# harp_timestamp_generator.net
KiCad netlist of a schematic drawn in EAGLE
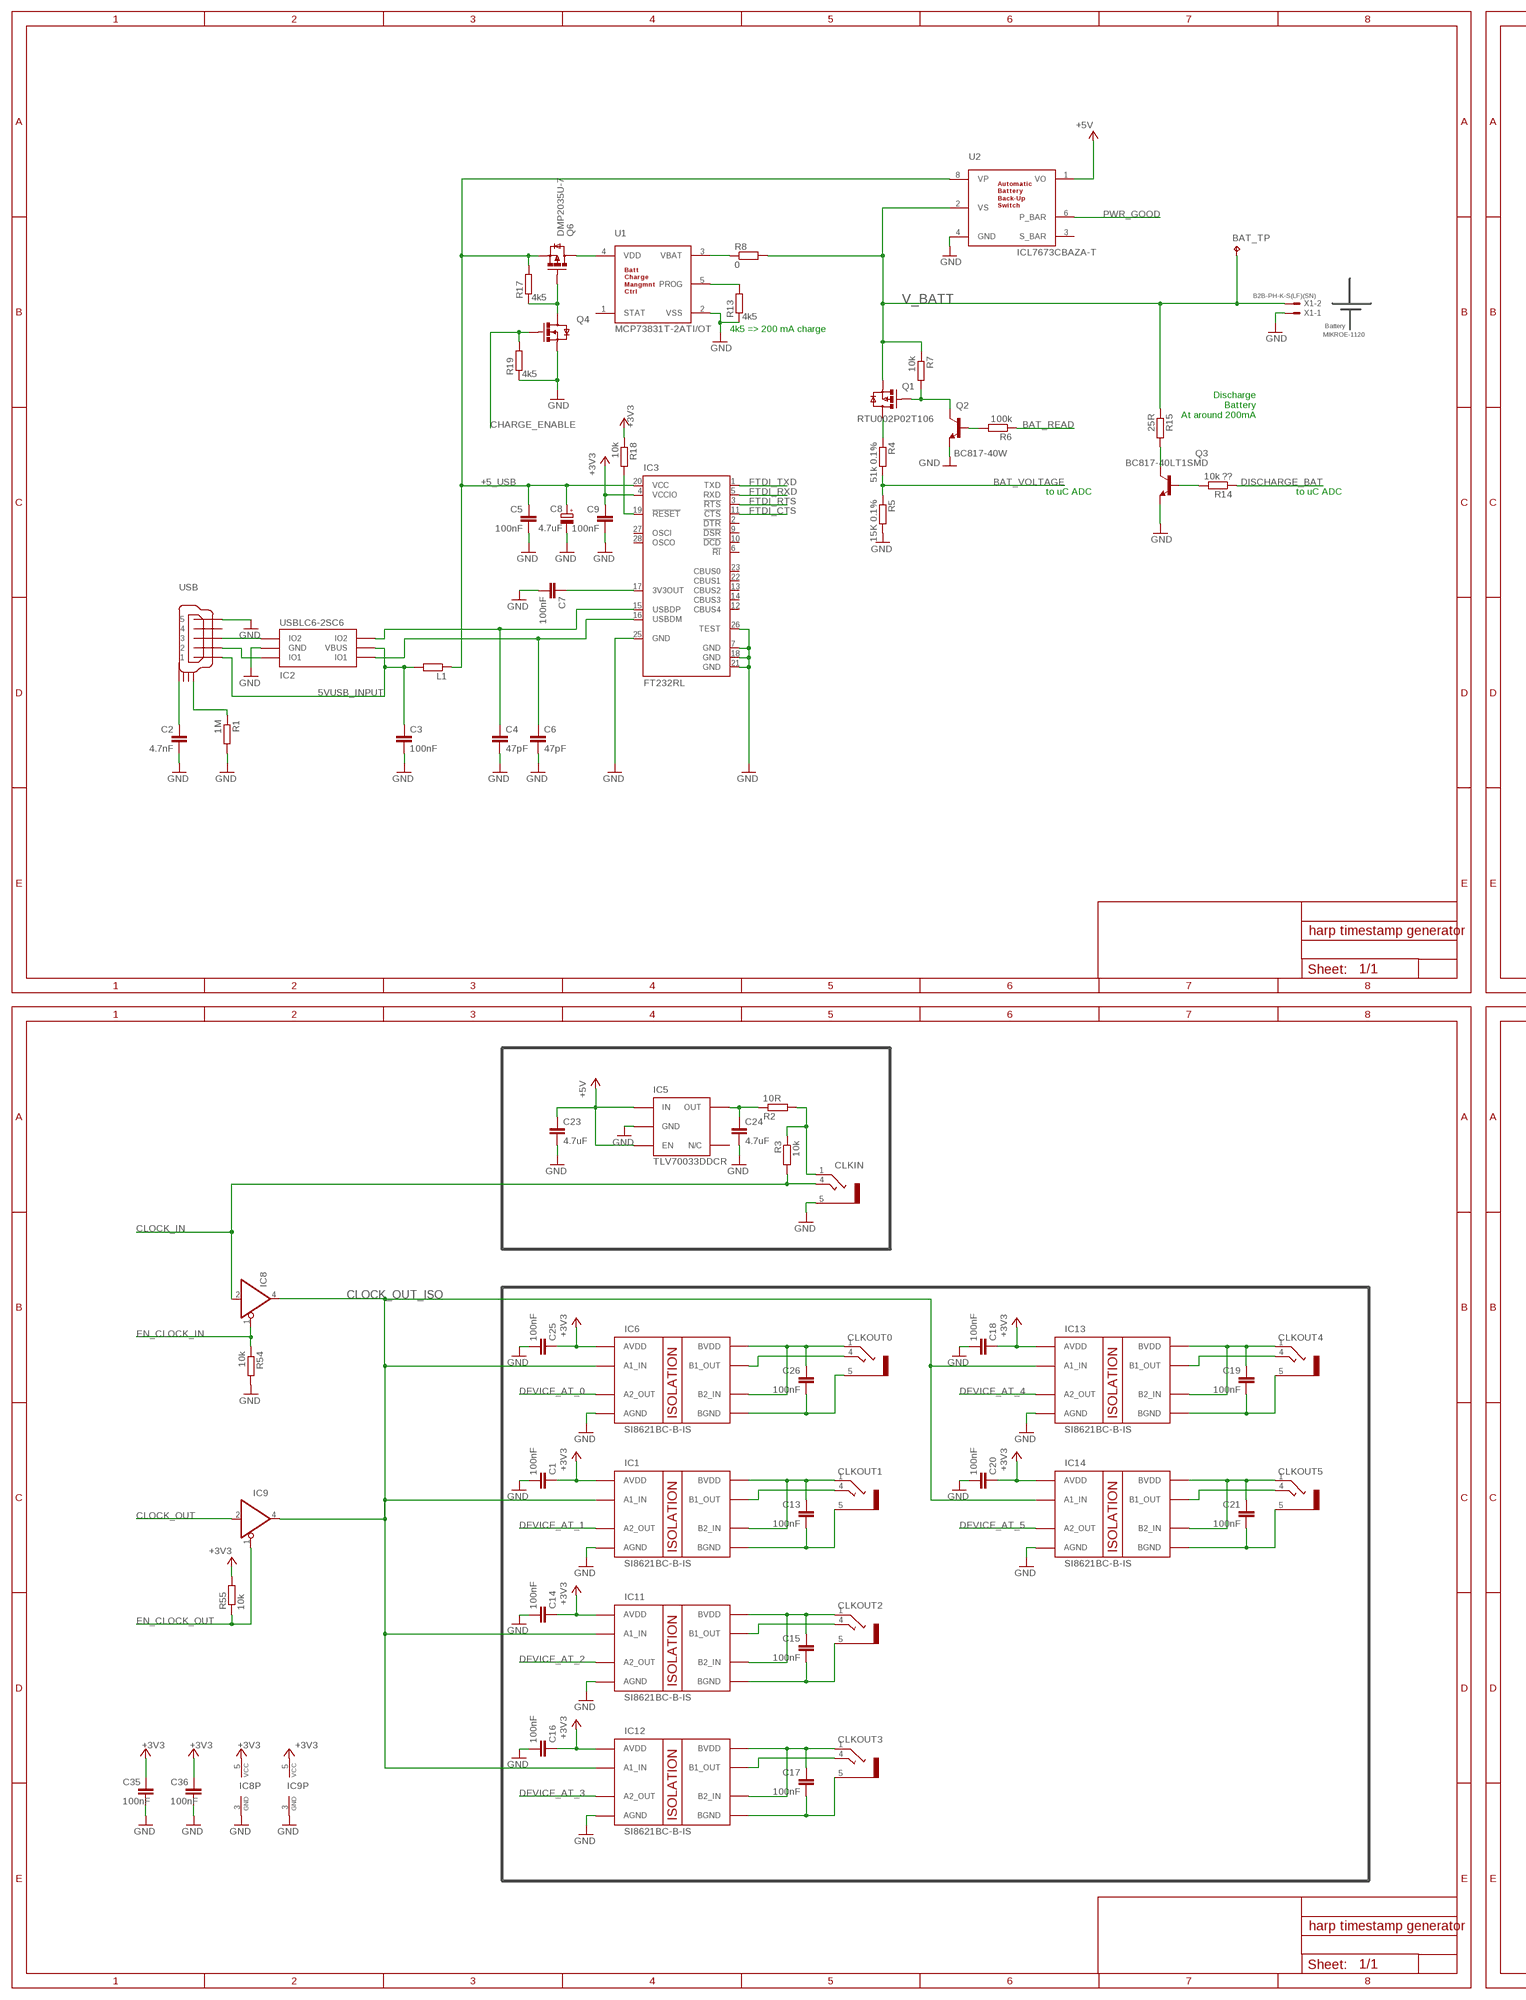
[diagram p0: schematic, sheet 1, part 1 of 3]
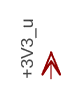
[diagram p1: schematic, sheet 1, part 2 of 3]
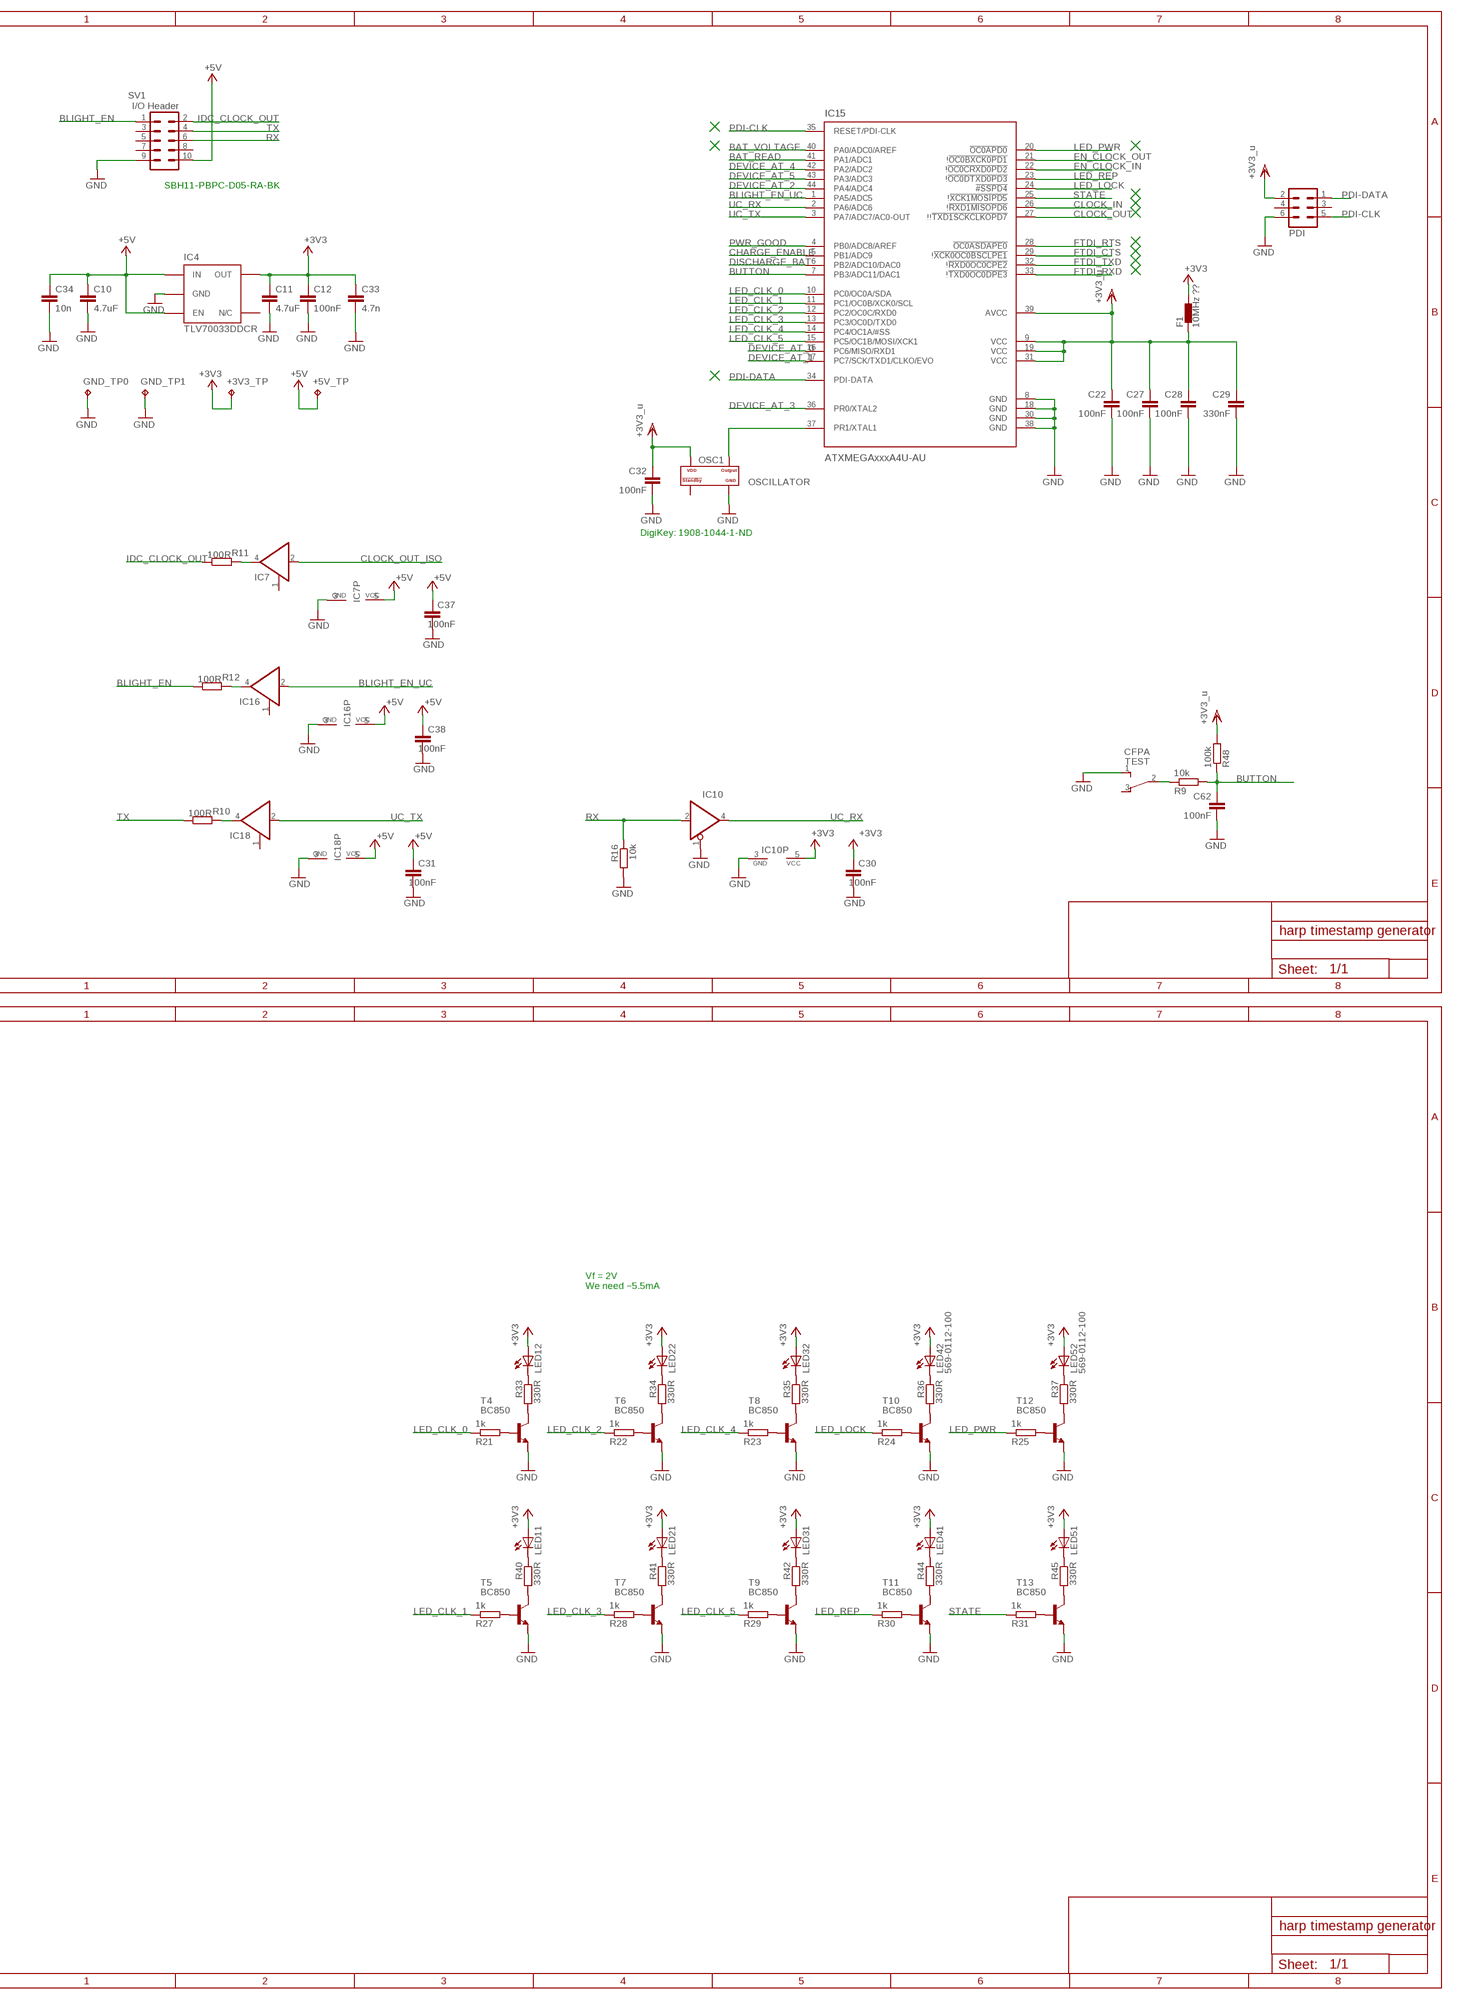
[diagram p2: schematic, sheet 1, part 3 of 3]

(export (version "E")
  (design (tool "Eeschema 10.0.6"))
  (components
    (comp (ref "+3V3_TP")
      (value "TPPAD1-13")
      (footprint "eagle-import:P1-13")
      (fields (field (name "MPN") "n.a."))
      (libsource (lib "eagle-import") (part "TPPAD1-13"))
    )
    (comp (ref "+5V_TP")
      (value "TPPAD1-13")
      (footprint "eagle-import:P1-13")
      (fields (field (name "MPN") "n.a."))
      (libsource (lib "eagle-import") (part "TPPAD1-13"))
    )
    (comp (ref "BAT_TP")
      (value "TPPAD1-13")
      (footprint "eagle-import:P1-13")
      (fields (field (name "MPN") "n.a."))
      (libsource (lib "eagle-import") (part "TPPAD1-13"))
    )
    (comp (ref "C1")
      (value "100nF")
      (footprint "eagle-import:C0402")
      (fields (field (name "MPN") "MC0402B104K160CT"))
      (libsource (lib "eagle-import") (part "C-EUC0402"))
    )
    (comp (ref "C2")
      (value "4.7nF")
      (footprint "eagle-import:C0402")
      (fields (field (name "MPN") "885012205084"))
      (libsource (lib "eagle-import") (part "C-EUC0402"))
    )
    (comp (ref "C3")
      (value "100nF")
      (footprint "eagle-import:C0402")
      (fields (field (name "MPN") "MC0402B104K160CT"))
      (libsource (lib "eagle-import") (part "C-EUC0402"))
    )
    (comp (ref "C4")
      (value "47pF")
      (footprint "eagle-import:C0402")
      (fields (field (name "MPN") "04025A470JAT2A"))
      (libsource (lib "eagle-import") (part "C-EUC0402"))
    )
    (comp (ref "C5")
      (value "100nF")
      (footprint "eagle-import:C0402")
      (fields (field (name "MPN") "MC0402B104K160CT"))
      (libsource (lib "eagle-import") (part "C-EUC0402"))
    )
    (comp (ref "C6")
      (value "47pF")
      (footprint "eagle-import:C0402")
      (fields (field (name "MPN") "04025A470JAT2A"))
      (libsource (lib "eagle-import") (part "C-EUC0402"))
    )
    (comp (ref "C7")
      (value "100nF")
      (footprint "eagle-import:C0402")
      (fields (field (name "MPN") "MC0402B104K160CT"))
      (libsource (lib "eagle-import") (part "C-EUC0402"))
    )
    (comp (ref "C8")
      (value "4.7uF")
      (footprint "eagle-import:A_3216-18W")
      (fields (field (name "MPN") "TAJA475K016UNJ"))
      (libsource (lib "eagle-import") (part "CPOL-EUA/3216-18W"))
    )
    (comp (ref "C9")
      (value "100nF")
      (footprint "eagle-import:C0402")
      (fields (field (name "MPN") "MC0402B104K160CT"))
      (libsource (lib "eagle-import") (part "C-EUC0402"))
    )
    (comp (ref "C10")
      (value "4.7uF")
      (footprint "eagle-import:C0603")
      (fields (field (name "MPN") "C1608X6S1C475K080AC"))
      (libsource (lib "eagle-import") (part "C-EUC0603"))
    )
    (comp (ref "C11")
      (value "4.7uF")
      (footprint "eagle-import:C0603")
      (fields (field (name "MPN") "C1608X6S1C475K080AC"))
      (libsource (lib "eagle-import") (part "C-EUC0603"))
    )
    (comp (ref "C12")
      (value "100nF")
      (footprint "eagle-import:C0402")
      (fields (field (name "MPN") "MC0402B104K160CT"))
      (libsource (lib "eagle-import") (part "C-EUC0402"))
    )
    (comp (ref "C13")
      (value "100nF")
      (footprint "eagle-import:C0402")
      (fields (field (name "MPN") "MC0402B104K160CT"))
      (libsource (lib "eagle-import") (part "C-EUC0402"))
    )
    (comp (ref "C14")
      (value "100nF")
      (footprint "eagle-import:C0402")
      (fields (field (name "MPN") "MC0402B104K160CT"))
      (libsource (lib "eagle-import") (part "C-EUC0402"))
    )
    (comp (ref "C15")
      (value "100nF")
      (footprint "eagle-import:C0402")
      (fields (field (name "MPN") "MC0402B104K160CT"))
      (libsource (lib "eagle-import") (part "C-EUC0402"))
    )
    (comp (ref "C16")
      (value "100nF")
      (footprint "eagle-import:C0402")
      (fields (field (name "MPN") "MC0402B104K160CT"))
      (libsource (lib "eagle-import") (part "C-EUC0402"))
    )
    (comp (ref "C17")
      (value "100nF")
      (footprint "eagle-import:C0402")
      (fields (field (name "MPN") "MC0402B104K160CT"))
      (libsource (lib "eagle-import") (part "C-EUC0402"))
    )
    (comp (ref "C18")
      (value "100nF")
      (footprint "eagle-import:C0402")
      (fields (field (name "MPN") "MC0402B104K160CT"))
      (libsource (lib "eagle-import") (part "C-EUC0402"))
    )
    (comp (ref "C19")
      (value "100nF")
      (footprint "eagle-import:C0402")
      (fields (field (name "MPN") "MC0402B104K160CT"))
      (libsource (lib "eagle-import") (part "C-EUC0402"))
    )
    (comp (ref "C20")
      (value "100nF")
      (footprint "eagle-import:C0402")
      (fields (field (name "MPN") "MC0402B104K160CT"))
      (libsource (lib "eagle-import") (part "C-EUC0402"))
    )
    (comp (ref "C21")
      (value "100nF")
      (footprint "eagle-import:C0402")
      (fields (field (name "MPN") "MC0402B104K160CT"))
      (libsource (lib "eagle-import") (part "C-EUC0402"))
    )
    (comp (ref "C22")
      (value "100nF")
      (footprint "eagle-import:C0402")
      (libsource (lib "eagle-import") (part "C-EUC0402"))
    )
    (comp (ref "C23")
      (value "4.7uF")
      (footprint "eagle-import:C0603")
      (fields (field (name "MPN") "C1608X6S1C475K080AC"))
      (libsource (lib "eagle-import") (part "C-EUC0603"))
    )
    (comp (ref "C24")
      (value "4.7uF")
      (footprint "eagle-import:C0603")
      (fields (field (name "MPN") "C1608X6S1C475K080AC"))
      (libsource (lib "eagle-import") (part "C-EUC0603"))
    )
    (comp (ref "C25")
      (value "100nF")
      (footprint "eagle-import:C0402")
      (fields (field (name "MPN") "MC0402B104K160CT"))
      (libsource (lib "eagle-import") (part "C-EUC0402"))
    )
    (comp (ref "C26")
      (value "100nF")
      (footprint "eagle-import:C0402")
      (fields (field (name "MPN") "MC0402B104K160CT"))
      (libsource (lib "eagle-import") (part "C-EUC0402"))
    )
    (comp (ref "C27")
      (value "100nF")
      (footprint "eagle-import:C0402")
      (libsource (lib "eagle-import") (part "C-EUC0402"))
    )
    (comp (ref "C28")
      (value "100nF")
      (footprint "eagle-import:C0402")
      (libsource (lib "eagle-import") (part "C-EUC0402"))
    )
    (comp (ref "C29")
      (value "330nF")
      (footprint "eagle-import:C0402")
      (libsource (lib "eagle-import") (part "C-EUC0402"))
    )
    (comp (ref "C30")
      (value "100nF")
      (footprint "eagle-import:C0402")
      (fields (field (name "MPN") "MC0402B104K160CT"))
      (libsource (lib "eagle-import") (part "C-EUC0402"))
    )
    (comp (ref "C31")
      (value "100nF")
      (footprint "eagle-import:C0402")
      (fields (field (name "MPN") "MC0402B104K160CT"))
      (libsource (lib "eagle-import") (part "C-EUC0402"))
    )
    (comp (ref "C32")
      (value "100nF")
      (footprint "eagle-import:C0402")
      (libsource (lib "eagle-import") (part "C-EUC0402"))
    )
    (comp (ref "C33")
      (value "4.7n")
      (footprint "eagle-import:C0402")
      (fields (field (name "MPN") "??"))
      (libsource (lib "eagle-import") (part "C-EUC0402"))
    )
    (comp (ref "C34")
      (value "10n")
      (footprint "eagle-import:C0402")
      (fields (field (name "MPN") "??"))
      (libsource (lib "eagle-import") (part "C-EUC0402"))
    )
    (comp (ref "C35")
      (value "100nF")
      (footprint "eagle-import:C0402")
      (fields (field (name "MPN") "MC0402B104K160CT"))
      (libsource (lib "eagle-import") (part "C-EUC0402"))
    )
    (comp (ref "C36")
      (value "100nF")
      (footprint "eagle-import:C0402")
      (fields (field (name "MPN") "MC0402B104K160CT"))
      (libsource (lib "eagle-import") (part "C-EUC0402"))
    )
    (comp (ref "C37")
      (value "100nF")
      (footprint "eagle-import:C0402")
      (fields (field (name "MPN") "MC0402B104K160CT"))
      (libsource (lib "eagle-import") (part "C-EUC0402"))
    )
    (comp (ref "C38")
      (value "100nF")
      (footprint "eagle-import:C0402")
      (fields (field (name "MPN") "MC0402B104K160CT"))
      (libsource (lib "eagle-import") (part "C-EUC0402"))
    )
    (comp (ref "C62")
      (value "100nF")
      (footprint "eagle-import:C0402")
      (libsource (lib "eagle-import") (part "C-EUC0402"))
    )
    (comp (ref "CLKIN")
      (value "CLCK_JACK")
      (footprint "eagle-import:35RASMT2BHNTRX")
      (fields (field (name "MPN") "35RASMT2BHNTRX"))
      (libsource (lib "eagle-import") (part "STEREO_JACK"))
    )
    (comp (ref "CLKOUT0")
      (value "CLCK_JACK")
      (footprint "eagle-import:35RASMT2BHNTRX")
      (fields (field (name "MPN") "35RASMT2BHNTRX"))
      (libsource (lib "eagle-import") (part "STEREO_JACK"))
    )
    (comp (ref "CLKOUT1")
      (value "CLCK_JACK")
      (footprint "eagle-import:35RASMT2BHNTRX")
      (fields (field (name "MPN") "35RASMT2BHNTRX"))
      (libsource (lib "eagle-import") (part "STEREO_JACK"))
    )
    (comp (ref "CLKOUT2")
      (value "CLCK_JACK")
      (footprint "eagle-import:35RASMT2BHNTRX")
      (fields (field (name "MPN") "35RASMT2BHNTRX"))
      (libsource (lib "eagle-import") (part "STEREO_JACK"))
    )
    (comp (ref "CLKOUT3")
      (value "CLCK_JACK")
      (footprint "eagle-import:35RASMT2BHNTRX")
      (fields (field (name "MPN") "35RASMT2BHNTRX"))
      (libsource (lib "eagle-import") (part "STEREO_JACK"))
    )
    (comp (ref "CLKOUT4")
      (value "CLCK_JACK")
      (footprint "eagle-import:35RASMT2BHNTRX")
      (fields (field (name "MPN") "35RASMT2BHNTRX"))
      (libsource (lib "eagle-import") (part "STEREO_JACK"))
    )
    (comp (ref "CLKOUT5")
      (value "CLCK_JACK")
      (footprint "eagle-import:35RASMT2BHNTRX")
      (fields (field (name "MPN") "35RASMT2BHNTRX"))
      (libsource (lib "eagle-import") (part "STEREO_JACK"))
    )
    (comp (ref "F1")
      (value "10MHz ??")
      (footprint "eagle-import:R0603")
      (libsource (lib "eagle-import") (part "BLM15HF0603"))
    )
    (comp (ref "GND_TP0")
      (value "TPPAD1-13")
      (footprint "eagle-import:P1-13")
      (fields (field (name "MPN") "n.a."))
      (libsource (lib "eagle-import") (part "TPPAD1-13"))
    )
    (comp (ref "GND_TP1")
      (value "TPPAD1-13")
      (footprint "eagle-import:P1-13")
      (fields (field (name "MPN") "n.a."))
      (libsource (lib "eagle-import") (part "TPPAD1-13"))
    )
    (comp (ref "IC1")
      (value "SI8621BC-B-IS")
      (footprint "eagle-import:SOIC8")
      (fields (field (name "MPN") "Si8621BC-B-IS"))
      (libsource (lib "eagle-import") (part "SI8621BC-B-IS"))
    )
    (comp (ref "IC2")
      (value "USBLC6-2SC6")
      (footprint "eagle-import:SOT23-6L")
      (libsource (lib "eagle-import") (part "USBLC6-2"))
    )
    (comp (ref "IC3")
      (value "FT232RL")
      (footprint "eagle-import:SSOP28")
      (fields (field (name "MPN") "FT232RL-REEL"))
      (libsource (lib "eagle-import") (part "FT232RL"))
    )
    (comp (ref "IC4")
      (value "TLV70033DDCR")
      (footprint "eagle-import:TSOT23-5")
      (libsource (lib "eagle-import") (part "TLV700XX"))
    )
    (comp (ref "IC5")
      (value "TLV70033DDCR")
      (footprint "eagle-import:TSOT23-5")
      (libsource (lib "eagle-import") (part "TLV700XX"))
    )
    (comp (ref "IC6")
      (value "SI8621BC-B-IS")
      (footprint "eagle-import:SOIC8")
      (fields (field (name "MPN") "Si8621BC-B-IS"))
      (libsource (lib "eagle-import") (part "SI8621BC-B-IS"))
    )
    (comp (ref "IC7")
      (value "74AHC1G126DCK")
      (footprint "eagle-import:SC70-5")
      (libsource (lib "eagle-import") (part "741G126DCKAHC"))
    )
    (comp (ref "IC8")
      (value "SN74LVC1G125DBVT")
      (footprint "eagle-import:SOT23-5")
      (fields (field (name "MPN") "SN74LVC1G125DBVT"))
      (libsource (lib "eagle-import") (part "741G125DBVAHC"))
    )
    (comp (ref "IC9")
      (value "SN74LVC1G125DBVT")
      (footprint "eagle-import:SOT23-5")
      (fields (field (name "MPN") "SN74LVC1G125DBVT"))
      (libsource (lib "eagle-import") (part "741G125DBVAHC"))
    )
    (comp (ref "IC10")
      (value "SN74LVC1G125DBVT")
      (footprint "eagle-import:SOT23-5")
      (fields (field (name "MPN") "SN74LVC1G125DBVT"))
      (libsource (lib "eagle-import") (part "741G125DBVAHC"))
    )
    (comp (ref "IC11")
      (value "SI8621BC-B-IS")
      (footprint "eagle-import:SOIC8")
      (fields (field (name "MPN") "Si8621BC-B-IS"))
      (libsource (lib "eagle-import") (part "SI8621BC-B-IS"))
    )
    (comp (ref "IC12")
      (value "SI8621BC-B-IS")
      (footprint "eagle-import:SOIC8")
      (fields (field (name "MPN") "Si8621BC-B-IS"))
      (libsource (lib "eagle-import") (part "SI8621BC-B-IS"))
    )
    (comp (ref "IC13")
      (value "SI8621BC-B-IS")
      (footprint "eagle-import:SOIC8")
      (fields (field (name "MPN") "Si8621BC-B-IS"))
      (libsource (lib "eagle-import") (part "SI8621BC-B-IS"))
    )
    (comp (ref "IC14")
      (value "SI8621BC-B-IS")
      (footprint "eagle-import:SOIC8")
      (fields (field (name "MPN") "Si8621BC-B-IS"))
      (libsource (lib "eagle-import") (part "SI8621BC-B-IS"))
    )
    (comp (ref "IC15")
      (value "ATXMEGAxxxA4U-AU")
      (footprint "eagle-import:QFP80P1200X1200X120-44N")
      (libsource (lib "eagle-import") (part "AT-XMEGA-XXA4-AU"))
    )
    (comp (ref "IC16")
      (value "74AHC1G126DCK")
      (footprint "eagle-import:SC70-5")
      (libsource (lib "eagle-import") (part "741G126DCKAHC"))
    )
    (comp (ref "IC18")
      (value "74AHC1G126DCK")
      (footprint "eagle-import:SC70-5")
      (libsource (lib "eagle-import") (part "741G126DCKAHC"))
    )
    (comp (ref "L1")
      (value "40R@100MHz")
      (footprint "eagle-import:R0805")
      (fields (field (name "MPN") "MI0805K400R-10"))
      (libsource (lib "eagle-import") (part "R-EU_R0805"))
    )
    (comp (ref "LED1")
      (value "569-0112-100")
      (footprint "eagle-import:569-011X-X00_LED_ARRAY")
      (fields (field (name "MPN") "5690-111-100F"))
      (libsource (lib "eagle-import") (part "LED_2X_VERTICAL"))
    )
    (comp (ref "LED2")
      (value "569-0112-100")
      (footprint "eagle-import:569-011X-X00_LED_ARRAY")
      (fields (field (name "MPN") "5690-111-100F"))
      (libsource (lib "eagle-import") (part "LED_2X_VERTICAL"))
    )
    (comp (ref "LED3")
      (value "569-0112-100")
      (footprint "eagle-import:569-011X-X00_LED_ARRAY")
      (fields (field (name "MPN") "5690-111-100F"))
      (libsource (lib "eagle-import") (part "LED_2X_VERTICAL"))
    )
    (comp (ref "LED4")
      (value "569-0112-100")
      (footprint "eagle-import:569-011X-X00_LED_ARRAY")
      (fields (field (name "MPN") "5690-111-100F"))
      (libsource (lib "eagle-import") (part "LED_2X_VERTICAL"))
    )
    (comp (ref "LED5")
      (value "569-0112-100")
      (footprint "eagle-import:569-011X-X00_LED_ARRAY")
      (fields (field (name "MPN") "5690-111-100F"))
      (libsource (lib "eagle-import") (part "LED_2X_VERTICAL"))
    )
    (comp (ref "OSC1")
      (value "OSCILLATOR")
      (footprint "eagle-import:OSCILLATOR_3.2X2.5")
      (libsource (lib "eagle-import") (part "OSCILLATOR"))
    )
    (comp (ref "PDI")
      (value "MA03-2")
      (footprint "eagle-import:MA03-2")
      (libsource (lib "eagle-import") (part "MA03-2"))
    )
    (comp (ref "Q1")
      (value "RTU002P02T106")
      (footprint "eagle-import:SOT323")
      (libsource (lib "eagle-import") (part "MOSFET-PCHANNEL-ROHM"))
    )
    (comp (ref "Q2")
      (value "BC817-40W")
      (footprint "eagle-import:SOT323-BEC")
      (libsource (lib "eagle-import") (part "BC817"))
    )
    (comp (ref "Q3")
      (value "BC817-40LT1SMD")
      (footprint "eagle-import:SOT23-BEC")
      (libsource (lib "eagle-import") (part "transistor-npn_398_BC817SMD-40LT1"))
    )
    (comp (ref "Q4")
      (value "DMG1012UW")
      (footprint "eagle-import:SOT323")
      (libsource (lib "eagle-import") (part "DMG1012UW"))
    )
    (comp (ref "Q6")
      (value "DMP2035U-7")
      (footprint "eagle-import:SOT323")
      (libsource (lib "eagle-import") (part "DMP2035U-7"))
    )
    (comp (ref "R1")
      (value "1M")
      (footprint "eagle-import:R0402")
      (fields (field (name "MPN") "CRCW04021M00FKED"))
      (libsource (lib "eagle-import") (part "R-EU_R0402"))
    )
    (comp (ref "R2")
      (value "10R")
      (footprint "eagle-import:R0402")
      (fields (field (name "MPN") "CRCW040210R0FKEDHP"))
      (libsource (lib "eagle-import") (part "R-EU_R0402"))
    )
    (comp (ref "R3")
      (value "10k")
      (footprint "eagle-import:R0402")
      (fields (field (name "MPN") "CRCW040210K0FKED"))
      (libsource (lib "eagle-import") (part "R-EU_R0402"))
    )
    (comp (ref "R4")
      (value "51k 0.1%")
      (footprint "eagle-import:R0402")
      (fields (field (name "MPN") "CRCW040210K0FKED"))
      (libsource (lib "eagle-import") (part "R-EU_R0402"))
    )
    (comp (ref "R5")
      (value "15K 0.1%")
      (footprint "eagle-import:R0402")
      (fields (field (name "MPN") "CRCW040210K0FKED"))
      (libsource (lib "eagle-import") (part "R-EU_R0402"))
    )
    (comp (ref "R6")
      (value "100k")
      (footprint "eagle-import:R0402")
      (fields (field (name "MPN") "CRCW040210K0FKED"))
      (libsource (lib "eagle-import") (part "R-EU_R0402"))
    )
    (comp (ref "R7")
      (value "10k")
      (footprint "eagle-import:R0402")
      (fields (field (name "MPN") "CRCW040210K0FKED"))
      (libsource (lib "eagle-import") (part "R-EU_R0402"))
    )
    (comp (ref "R8")
      (value "0")
      (footprint "eagle-import:R0402")
      (fields (field (name "MPN") "CRCW040210K0FKED"))
      (libsource (lib "eagle-import") (part "R-EU_R0402"))
    )
    (comp (ref "R9")
      (value "10k")
      (footprint "eagle-import:R0402")
      (libsource (lib "eagle-import") (part "R-EU_R0402"))
    )
    (comp (ref "R10")
      (value "100R")
      (footprint "eagle-import:R0603")
      (fields (field (name "MPN") "CRCW0603100RFKEAHP"))
      (libsource (lib "eagle-import") (part "R-EU_R0603"))
    )
    (comp (ref "R11")
      (value "100R")
      (footprint "eagle-import:R0603")
      (fields (field (name "MPN") "CRCW0603100RFKEAHP"))
      (libsource (lib "eagle-import") (part "R-EU_R0603"))
    )
    (comp (ref "R12")
      (value "100R")
      (footprint "eagle-import:R0603")
      (fields (field (name "MPN") "CRCW0603100RFKEAHP"))
      (libsource (lib "eagle-import") (part "R-EU_R0603"))
    )
    (comp (ref "R13")
      (value "4k5")
      (footprint "eagle-import:R0402")
      (fields (field (name "MPN") "22k !!!"))
      (libsource (lib "eagle-import") (part "R-EU_R0402"))
    )
    (comp (ref "R14")
      (value "10k ??")
      (footprint "eagle-import:R0402")
      (fields (field (name "MPN") "???"))
      (libsource (lib "eagle-import") (part "R-EU_R0402"))
    )
    (comp (ref "R15")
      (value "25R")
      (footprint "eagle-import:R2512")
      (fields (field (name "MPN") "???"))
      (libsource (lib "eagle-import") (part "R-EU_R2512"))
    )
    (comp (ref "R16")
      (value "10k")
      (footprint "eagle-import:R0402")
      (fields (field (name "MPN") "CRCW040210K0FKED"))
      (libsource (lib "eagle-import") (part "R-EU_R0402"))
    )
    (comp (ref "R17")
      (value "4k5")
      (footprint "eagle-import:R0402")
      (fields (field (name "MPN") "22k !!!"))
      (libsource (lib "eagle-import") (part "R-EU_R0402"))
    )
    (comp (ref "R18")
      (value "10k")
      (footprint "eagle-import:R0402")
      (fields (field (name "MPN") "CRCW040210K0FKED"))
      (libsource (lib "eagle-import") (part "R-EU_R0402"))
    )
    (comp (ref "R19")
      (value "4k5")
      (footprint "eagle-import:R0402")
      (fields (field (name "MPN") "22k !!!"))
      (libsource (lib "eagle-import") (part "R-EU_R0402"))
    )
    (comp (ref "R21")
      (value "1k")
      (footprint "eagle-import:R0402")
      (fields (field (name "MPN") "CRCW04021K00FKED"))
      (libsource (lib "eagle-import") (part "R-EU_R0402"))
    )
    (comp (ref "R22")
      (value "1k")
      (footprint "eagle-import:R0402")
      (fields (field (name "MPN") "CRCW04021K00FKED"))
      (libsource (lib "eagle-import") (part "R-EU_R0402"))
    )
    (comp (ref "R23")
      (value "1k")
      (footprint "eagle-import:R0402")
      (fields (field (name "MPN") "CRCW04021K00FKED"))
      (libsource (lib "eagle-import") (part "R-EU_R0402"))
    )
    (comp (ref "R24")
      (value "1k")
      (footprint "eagle-import:R0402")
      (fields (field (name "MPN") "CRCW04021K00FKED"))
      (libsource (lib "eagle-import") (part "R-EU_R0402"))
    )
    (comp (ref "R25")
      (value "1k")
      (footprint "eagle-import:R0402")
      (fields (field (name "MPN") "CRCW04021K00FKED"))
      (libsource (lib "eagle-import") (part "R-EU_R0402"))
    )
    (comp (ref "R27")
      (value "1k")
      (footprint "eagle-import:R0402")
      (fields (field (name "MPN") "CRCW04021K00FKED"))
      (libsource (lib "eagle-import") (part "R-EU_R0402"))
    )
    (comp (ref "R28")
      (value "1k")
      (footprint "eagle-import:R0402")
      (fields (field (name "MPN") "CRCW04021K00FKED"))
      (libsource (lib "eagle-import") (part "R-EU_R0402"))
    )
    (comp (ref "R29")
      (value "1k")
      (footprint "eagle-import:R0402")
      (fields (field (name "MPN") "CRCW04021K00FKED"))
      (libsource (lib "eagle-import") (part "R-EU_R0402"))
    )
    (comp (ref "R30")
      (value "1k")
      (footprint "eagle-import:R0402")
      (fields (field (name "MPN") "CRCW04021K00FKED"))
      (libsource (lib "eagle-import") (part "R-EU_R0402"))
    )
    (comp (ref "R31")
      (value "1k")
      (footprint "eagle-import:R0402")
      (fields (field (name "MPN") "CRCW04021K00FKED"))
      (libsource (lib "eagle-import") (part "R-EU_R0402"))
    )
    (comp (ref "R33")
      (value "330R")
      (footprint "eagle-import:R0402")
      (fields (field (name "MPN") "RC0402FR-07330RL "))
      (libsource (lib "eagle-import") (part "R-EU_R0402"))
    )
    (comp (ref "R34")
      (value "330R")
      (footprint "eagle-import:R0402")
      (fields (field (name "MPN") "RC0402FR-07330RL "))
      (libsource (lib "eagle-import") (part "R-EU_R0402"))
    )
    (comp (ref "R35")
      (value "330R")
      (footprint "eagle-import:R0402")
      (fields (field (name "MPN") "RC0402FR-07330RL "))
      (libsource (lib "eagle-import") (part "R-EU_R0402"))
    )
    (comp (ref "R36")
      (value "330R")
      (footprint "eagle-import:R0402")
      (fields (field (name "MPN") "RC0402FR-07330RL "))
      (libsource (lib "eagle-import") (part "R-EU_R0402"))
    )
    (comp (ref "R37")
      (value "330R")
      (footprint "eagle-import:R0402")
      (fields (field (name "MPN") "RC0402FR-07330RL "))
      (libsource (lib "eagle-import") (part "R-EU_R0402"))
    )
    (comp (ref "R40")
      (value "330R")
      (footprint "eagle-import:R0402")
      (fields (field (name "MPN") "RC0402FR-07330RL "))
      (libsource (lib "eagle-import") (part "R-EU_R0402"))
    )
    (comp (ref "R41")
      (value "330R")
      (footprint "eagle-import:R0402")
      (fields (field (name "MPN") "RC0402FR-07330RL "))
      (libsource (lib "eagle-import") (part "R-EU_R0402"))
    )
    (comp (ref "R42")
      (value "330R")
      (footprint "eagle-import:R0402")
      (fields (field (name "MPN") "RC0402FR-07330RL "))
      (libsource (lib "eagle-import") (part "R-EU_R0402"))
    )
    (comp (ref "R44")
      (value "330R")
      (footprint "eagle-import:R0402")
      (fields (field (name "MPN") "RC0402FR-07330RL "))
      (libsource (lib "eagle-import") (part "R-EU_R0402"))
    )
    (comp (ref "R45")
      (value "330R")
      (footprint "eagle-import:R0402")
      (fields (field (name "MPN") "RC0402FR-07330RL "))
      (libsource (lib "eagle-import") (part "R-EU_R0402"))
    )
    (comp (ref "R48")
      (value "100k")
      (footprint "eagle-import:R0402")
      (libsource (lib "eagle-import") (part "R-EU_R0402"))
    )
    (comp (ref "R54")
      (value "10k")
      (footprint "eagle-import:R0402")
      (fields (field (name "MPN") "CRCW040210K0FKED"))
      (libsource (lib "eagle-import") (part "R-EU_R0402"))
    )
    (comp (ref "R55")
      (value "10k")
      (footprint "eagle-import:R0402")
      (fields (field (name "MPN") "CRCW040210K0FKED"))
      (libsource (lib "eagle-import") (part "R-EU_R0402"))
    )
    (comp (ref "SV1")
      (value "I/O Header")
      (footprint "eagle-import:ML10L")
      (fields (field (name "MPN") "SBH11-PBPC-D05-RA-BK"))
      (libsource (lib "eagle-import") (part "ML10L"))
    )
    (comp (ref "T4")
      (value "BC850")
      (footprint "eagle-import:SOT23")
      (fields (field (name "MPN") "BC850C,215"))
      (libsource (lib "eagle-import") (part "BC850"))
    )
    (comp (ref "T5")
      (value "BC850")
      (footprint "eagle-import:SOT23")
      (fields (field (name "MPN") "BC850C,215"))
      (libsource (lib "eagle-import") (part "BC850"))
    )
    (comp (ref "T6")
      (value "BC850")
      (footprint "eagle-import:SOT23")
      (fields (field (name "MPN") "BC850C,215"))
      (libsource (lib "eagle-import") (part "BC850"))
    )
    (comp (ref "T7")
      (value "BC850")
      (footprint "eagle-import:SOT23")
      (fields (field (name "MPN") "BC850C,215"))
      (libsource (lib "eagle-import") (part "BC850"))
    )
    (comp (ref "T8")
      (value "BC850")
      (footprint "eagle-import:SOT23")
      (fields (field (name "MPN") "BC850C,215"))
      (libsource (lib "eagle-import") (part "BC850"))
    )
    (comp (ref "T9")
      (value "BC850")
      (footprint "eagle-import:SOT23")
      (fields (field (name "MPN") "BC850C,215"))
      (libsource (lib "eagle-import") (part "BC850"))
    )
    (comp (ref "T10")
      (value "BC850")
      (footprint "eagle-import:SOT23")
      (fields (field (name "MPN") "BC850C,215"))
      (libsource (lib "eagle-import") (part "BC850"))
    )
    (comp (ref "T11")
      (value "BC850")
      (footprint "eagle-import:SOT23")
      (fields (field (name "MPN") "BC850C,215"))
      (libsource (lib "eagle-import") (part "BC850"))
    )
    (comp (ref "T12")
      (value "BC850")
      (footprint "eagle-import:SOT23")
      (fields (field (name "MPN") "BC850C,215"))
      (libsource (lib "eagle-import") (part "BC850"))
    )
    (comp (ref "T13")
      (value "BC850")
      (footprint "eagle-import:SOT23")
      (fields (field (name "MPN") "BC850C,215"))
      (libsource (lib "eagle-import") (part "BC850"))
    )
    (comp (ref "TEST")
      (value "CFPA")
      (footprint "eagle-import:CFPA")
      (libsource (lib "eagle-import") (part "SPDT_CFPA"))
    )
    (comp (ref "U1")
      (value "MCP73831T-2ATI/OT")
      (footprint "eagle-import:TSOT23-5")
      (fields (field (name "MPN") "MCP73831T-2ATI/OT"))
      (libsource (lib "eagle-import") (part "MCP73831T-2ATI/OT"))
    )
    (comp (ref "U2")
      (value "ICL7673CBAZA-T")
      (footprint "eagle-import:SOIC8")
      (libsource (lib "eagle-import") (part "ICL7673CBAZA-T"))
    )
    (comp (ref "USB")
      (value "mini USB")
      (footprint "eagle-import:240-0002-1")
      (fields (field (name "MPN") "UX60-MB-5S8 "))
      (libsource (lib "eagle-import") (part "USB_MINI_B"))
    )
    (comp (ref "X1")
      (value "B2B-PH-K-S(LF)(SN)")
      (footprint "eagle-import:JST-XH-02-PACKAGE-ROUND-PAD")
      (libsource (lib "eagle-import") (part "JST-XH-02-PIN-ROUND-PAD"))
    )
  )
  (nets
    (net (code "1") (name "+3V3") (class "Default")
      (node (ref "+3V3_TP") (pin "TP") (pinfunction "TP_TP") (pintype "input"))
      (node (ref "C1") (pin "1") (pinfunction "1_1") (pintype "passive"))
      (node (ref "C11") (pin "1") (pinfunction "1_1") (pintype "passive"))
      (node (ref "C12") (pin "1") (pinfunction "1_1") (pintype "passive"))
      (node (ref "C14") (pin "1") (pinfunction "1_1") (pintype "passive"))
      (node (ref "C16") (pin "1") (pinfunction "1_1") (pintype "passive"))
      (node (ref "C18") (pin "1") (pinfunction "1_1") (pintype "passive"))
      (node (ref "C20") (pin "1") (pinfunction "1_1") (pintype "passive"))
      (node (ref "C25") (pin "1") (pinfunction "1_1") (pintype "passive"))
      (node (ref "C30") (pin "1") (pinfunction "1_1") (pintype "passive"))
      (node (ref "C33") (pin "1") (pinfunction "1_1") (pintype "passive"))
      (node (ref "C35") (pin "1") (pinfunction "1_1") (pintype "passive"))
      (node (ref "C36") (pin "1") (pinfunction "1_1") (pintype "passive"))
      (node (ref "C9") (pin "1") (pinfunction "1_1") (pintype "passive"))
      (node (ref "F1") (pin "2") (pinfunction "2_2") (pintype "passive"))
      (node (ref "IC1") (pin "1") (pinfunction "AVDD_1") (pintype "bidirectional"))
      (node (ref "IC10") (pin "5") (pinfunction "VCC_5") (pintype "power_in"))
      (node (ref "IC11") (pin "1") (pinfunction "AVDD_1") (pintype "bidirectional"))
      (node (ref "IC12") (pin "1") (pinfunction "AVDD_1") (pintype "bidirectional"))
      (node (ref "IC13") (pin "1") (pinfunction "AVDD_1") (pintype "bidirectional"))
      (node (ref "IC14") (pin "1") (pinfunction "AVDD_1") (pintype "bidirectional"))
      (node (ref "IC3") (pin "4") (pinfunction "VCCIO_4") (pintype "power_in"))
      (node (ref "IC4") (pin "5") (pinfunction "OUT_5") (pintype "bidirectional"))
      (node (ref "IC6") (pin "1") (pinfunction "AVDD_1") (pintype "bidirectional"))
      (node (ref "IC8") (pin "5") (pinfunction "VCC_5") (pintype "power_in"))
      (node (ref "IC9") (pin "5") (pinfunction "VCC_5") (pintype "power_in"))
      (node (ref "LED1") (pin "A1") (pinfunction "A_A1") (pintype "passive"))
      (node (ref "LED1") (pin "A2") (pinfunction "A_A2") (pintype "passive"))
      (node (ref "LED2") (pin "A1") (pinfunction "A_A1") (pintype "passive"))
      (node (ref "LED2") (pin "A2") (pinfunction "A_A2") (pintype "passive"))
      (node (ref "LED3") (pin "A1") (pinfunction "A_A1") (pintype "passive"))
      (node (ref "LED3") (pin "A2") (pinfunction "A_A2") (pintype "passive"))
      (node (ref "LED4") (pin "A1") (pinfunction "A_A1") (pintype "passive"))
      (node (ref "LED4") (pin "A2") (pinfunction "A_A2") (pintype "passive"))
      (node (ref "LED5") (pin "A1") (pinfunction "A_A1") (pintype "passive"))
      (node (ref "LED5") (pin "A2") (pinfunction "A_A2") (pintype "passive"))
      (node (ref "R18") (pin "1") (pinfunction "1_1") (pintype "passive"))
      (node (ref "R55") (pin "2") (pinfunction "2_2") (pintype "passive"))
    )
    (net (code "2") (name "+3V3_u") (class "Default")
      (node (ref "C22") (pin "1") (pinfunction "1_1") (pintype "passive"))
      (node (ref "C27") (pin "1") (pinfunction "1_1") (pintype "passive"))
      (node (ref "C28") (pin "1") (pinfunction "1_1") (pintype "passive"))
      (node (ref "C29") (pin "1") (pinfunction "1_1") (pintype "passive"))
      (node (ref "C32") (pin "1") (pinfunction "1_1") (pintype "passive"))
      (node (ref "F1") (pin "1") (pinfunction "1_1") (pintype "passive"))
      (node (ref "IC15") (pin "19") (pinfunction "VCC_19") (pintype "power_in"))
      (node (ref "IC15") (pin "31") (pinfunction "VCC_31") (pintype "power_in"))
      (node (ref "IC15") (pin "39") (pinfunction "AVCC_39") (pintype "power_in"))
      (node (ref "IC15") (pin "9") (pinfunction "VCC_9") (pintype "power_in"))
      (node (ref "OSC1") (pin "P$4") (pinfunction "VDD_P$4") (pintype "passive"))
      (node (ref "PDI") (pin "2") (pinfunction "2_2") (pintype "passive"))
      (node (ref "R48") (pin "2") (pinfunction "2_2") (pintype "passive"))
    )
    (net (code "3") (name "+5V") (class "Default")
      (node (ref "+5V_TP") (pin "TP") (pinfunction "TP_TP") (pintype "input"))
      (node (ref "C10") (pin "1") (pinfunction "1_1") (pintype "passive"))
      (node (ref "C23") (pin "1") (pinfunction "1_1") (pintype "passive"))
      (node (ref "C31") (pin "1") (pinfunction "1_1") (pintype "passive"))
      (node (ref "C34") (pin "1") (pinfunction "1_1") (pintype "passive"))
      (node (ref "C37") (pin "1") (pinfunction "1_1") (pintype "passive"))
      (node (ref "C38") (pin "1") (pinfunction "1_1") (pintype "passive"))
      (node (ref "IC16") (pin "5") (pinfunction "VCC_5") (pintype "power_in"))
      (node (ref "IC18") (pin "5") (pinfunction "VCC_5") (pintype "power_in"))
      (node (ref "IC4") (pin "1") (pinfunction "IN_1") (pintype "bidirectional"))
      (node (ref "IC4") (pin "3") (pinfunction "EN_3") (pintype "bidirectional"))
      (node (ref "IC5") (pin "1") (pinfunction "IN_1") (pintype "bidirectional"))
      (node (ref "IC5") (pin "3") (pinfunction "EN_3") (pintype "bidirectional"))
      (node (ref "IC7") (pin "5") (pinfunction "VCC_5") (pintype "power_in"))
      (node (ref "SV1") (pin "10") (pinfunction "10_10") (pintype "passive"))
      (node (ref "U2") (pin "1") (pinfunction "VO_1") (pintype "bidirectional"))
    )
    (net (code "4") (name "/+5_USB") (class "Default")
      (node (ref "C5") (pin "1") (pinfunction "1_1") (pintype "passive"))
      (node (ref "C8") (pin "+") (pinfunction "+_+") (pintype "passive"))
      (node (ref "IC3") (pin "20") (pinfunction "VCC_20") (pintype "power_in"))
      (node (ref "L1") (pin "1") (pinfunction "1_1") (pintype "passive"))
      (node (ref "Q6") (pin "1") (pinfunction "S_1") (pintype "passive"))
      (node (ref "R17") (pin "2") (pinfunction "2_2") (pintype "passive"))
      (node (ref "U2") (pin "8") (pinfunction "VP_8") (pintype "bidirectional"))
    )
    (net (code "5") (name "/5VUSB_INPUT") (class "Default")
      (node (ref "C3") (pin "1") (pinfunction "1_1") (pintype "passive"))
      (node (ref "IC2") (pin "P$5") (pinfunction "VBUS_P$5") (pintype "bidirectional"))
      (node (ref "L1") (pin "2") (pinfunction "2_2") (pintype "passive"))
      (node (ref "USB") (pin "P$1") (pinfunction "1_P$1") (pintype "bidirectional"))
    )
    (net (code "6") (name "/BAT_READ") (class "Default")
      (node (ref "IC15") (pin "41") (pinfunction "PA1/ADC1_41") (pintype "bidirectional"))
      (node (ref "R6") (pin "1") (pinfunction "1_1") (pintype "passive"))
    )
    (net (code "7") (name "/BAT_VOLTAGE") (class "Default")
      (node (ref "IC15") (pin "40") (pinfunction "PA0/ADC0/AREF_40") (pintype "bidirectional"))
      (node (ref "R4") (pin "2") (pinfunction "2_2") (pintype "passive"))
      (node (ref "R5") (pin "1") (pinfunction "1_1") (pintype "passive"))
    )
    (net (code "8") (name "/BLIGHT_EN") (class "Default")
      (node (ref "R12") (pin "1") (pinfunction "1_1") (pintype "passive"))
      (node (ref "SV1") (pin "1") (pinfunction "1_1") (pintype "passive"))
    )
    (net (code "9") (name "/BLIGHT_EN_UC") (class "Default")
      (node (ref "IC15") (pin "1") (pinfunction "PA5/ADC5_1") (pintype "bidirectional"))
      (node (ref "IC16") (pin "2") (pinfunction "I_2") (pintype "input"))
    )
    (net (code "10") (name "/BUTTON") (class "Default")
      (node (ref "C62") (pin "1") (pinfunction "1_1") (pintype "passive"))
      (node (ref "IC15") (pin "7") (pinfunction "PB3/ADC11/DAC1_7") (pintype "bidirectional"))
      (node (ref "R48") (pin "1") (pinfunction "1_1") (pintype "passive"))
      (node (ref "R9") (pin "2") (pinfunction "2_2") (pintype "passive"))
    )
    (net (code "11") (name "/CHARGE_ENABLE") (class "Default")
      (node (ref "IC15") (pin "5") (pinfunction "PB1/ADC9_5") (pintype "bidirectional"))
      (node (ref "Q4") (pin "2") (pinfunction "G_2") (pintype "passive"))
      (node (ref "R19") (pin "2") (pinfunction "2_2") (pintype "passive"))
    )
    (net (code "12") (name "/CLOCK_IN") (class "Default")
      (node (ref "CLKIN") (pin "4") (pinfunction "4_4") (pintype "passive"))
      (node (ref "IC15") (pin "26") (pinfunction "~RXD1MISOPD6_26") (pintype "bidirectional"))
      (node (ref "IC8") (pin "2") (pinfunction "I_2") (pintype "input"))
      (node (ref "R3") (pin "2") (pinfunction "2_2") (pintype "passive"))
    )
    (net (code "13") (name "/CLOCK_OUT") (class "Default")
      (node (ref "IC15") (pin "27") (pinfunction "~~{TXD1SCKCLKOPD7}_27") (pintype "bidirectional"))
      (node (ref "IC9") (pin "2") (pinfunction "I_2") (pintype "input"))
    )
    (net (code "14") (name "/CLOCK_OUT_ISO") (class "Default")
      (node (ref "IC1") (pin "2") (pinfunction "A1_IN_2") (pintype "bidirectional"))
      (node (ref "IC11") (pin "2") (pinfunction "A1_IN_2") (pintype "bidirectional"))
      (node (ref "IC12") (pin "2") (pinfunction "A1_IN_2") (pintype "bidirectional"))
      (node (ref "IC13") (pin "2") (pinfunction "A1_IN_2") (pintype "bidirectional"))
      (node (ref "IC14") (pin "2") (pinfunction "A1_IN_2") (pintype "bidirectional"))
      (node (ref "IC6") (pin "2") (pinfunction "A1_IN_2") (pintype "bidirectional"))
      (node (ref "IC7") (pin "2") (pinfunction "I_2") (pintype "input"))
      (node (ref "IC8") (pin "4") (pinfunction "O_4") (pintype "tri_state"))
      (node (ref "IC9") (pin "4") (pinfunction "O_4") (pintype "tri_state"))
    )
    (net (code "15") (name "/DEVICE_AT_0") (class "Default")
      (node (ref "IC15") (pin "16") (pinfunction "PC6/MISO/RXD1_16") (pintype "bidirectional"))
      (node (ref "IC6") (pin "3") (pinfunction "A2_OUT_3") (pintype "bidirectional"))
    )
    (net (code "16") (name "/DEVICE_AT_1") (class "Default")
      (node (ref "IC1") (pin "3") (pinfunction "A2_OUT_3") (pintype "bidirectional"))
      (node (ref "IC15") (pin "17") (pinfunction "PC7/SCK/TXD1/CLKO/EVO_17") (pintype "bidirectional"))
    )
    (net (code "17") (name "/DEVICE_AT_2") (class "Default")
      (node (ref "IC11") (pin "3") (pinfunction "A2_OUT_3") (pintype "bidirectional"))
      (node (ref "IC15") (pin "44") (pinfunction "PA4/ADC4_44") (pintype "bidirectional"))
    )
    (net (code "18") (name "/DEVICE_AT_3") (class "Default")
      (node (ref "IC12") (pin "3") (pinfunction "A2_OUT_3") (pintype "bidirectional"))
      (node (ref "IC15") (pin "36") (pinfunction "PR0/XTAL2_36") (pintype "bidirectional"))
    )
    (net (code "19") (name "/DEVICE_AT_4") (class "Default")
      (node (ref "IC13") (pin "3") (pinfunction "A2_OUT_3") (pintype "bidirectional"))
      (node (ref "IC15") (pin "42") (pinfunction "PA2/ADC2_42") (pintype "bidirectional"))
    )
    (net (code "20") (name "/DEVICE_AT_5") (class "Default")
      (node (ref "IC14") (pin "3") (pinfunction "A2_OUT_3") (pintype "bidirectional"))
      (node (ref "IC15") (pin "43") (pinfunction "PA3/ADC3_43") (pintype "bidirectional"))
    )
    (net (code "21") (name "/DISCHARGE_BAT") (class "Default")
      (node (ref "IC15") (pin "6") (pinfunction "PB2/ADC10/DAC0_6") (pintype "bidirectional"))
      (node (ref "R14") (pin "1") (pinfunction "1_1") (pintype "passive"))
    )
    (net (code "22") (name "/EN_CLOCK_IN") (class "Default")
      (node (ref "IC15") (pin "22") (pinfunction "~OC0CRXD0PD2_22") (pintype "bidirectional"))
      (node (ref "IC8") (pin "1") (pinfunction "OE_1") (pintype "input"))
      (node (ref "R54") (pin "1") (pinfunction "1_1") (pintype "passive"))
    )
    (net (code "23") (name "/EN_CLOCK_OUT") (class "Default")
      (node (ref "IC15") (pin "21") (pinfunction "~OC0BXCK0PD1_21") (pintype "bidirectional"))
      (node (ref "IC9") (pin "1") (pinfunction "OE_1") (pintype "input"))
      (node (ref "R55") (pin "1") (pinfunction "1_1") (pintype "passive"))
    )
    (net (code "24") (name "/FTDI_CTS") (class "Default")
      (node (ref "IC15") (pin "29") (pinfunction "~XCK0OC0BSCLPE1_29") (pintype "bidirectional"))
      (node (ref "IC3") (pin "11") (pinfunction "~{CTS}_11") (pintype "input"))
    )
    (net (code "25") (name "/FTDI_RTS") (class "Default")
      (node (ref "IC15") (pin "28") (pinfunction "~{OC0ASDAPE0}_28") (pintype "bidirectional"))
      (node (ref "IC3") (pin "3") (pinfunction "~{RTS}_3") (pintype "output"))
    )
    (net (code "26") (name "/FTDI_RXD") (class "Default")
      (node (ref "IC15") (pin "33") (pinfunction "~TXD0OC0DPE3_33") (pintype "bidirectional"))
      (node (ref "IC3") (pin "5") (pinfunction "RXD_5") (pintype "input"))
    )
    (net (code "27") (name "/FTDI_TXD") (class "Default")
      (node (ref "IC15") (pin "32") (pinfunction "~RXD0OC0CPE2_32") (pintype "bidirectional"))
      (node (ref "IC3") (pin "1") (pinfunction "TXD_1") (pintype "output"))
    )
    (net (code "28") (name "/IDC_CLOCK_OUT") (class "Default")
      (node (ref "R11") (pin "1") (pinfunction "1_1") (pintype "passive"))
      (node (ref "SV1") (pin "2") (pinfunction "2_2") (pintype "passive"))
    )
    (net (code "29") (name "/LED_CLK_0") (class "Default")
      (node (ref "IC15") (pin "10") (pinfunction "PC0/OC0A/SDA_10") (pintype "bidirectional"))
      (node (ref "R21") (pin "1") (pinfunction "1_1") (pintype "passive"))
    )
    (net (code "30") (name "/LED_CLK_1") (class "Default")
      (node (ref "IC15") (pin "11") (pinfunction "PC1/OC0B/XCK0/SCL_11") (pintype "bidirectional"))
      (node (ref "R27") (pin "1") (pinfunction "1_1") (pintype "passive"))
    )
    (net (code "31") (name "/LED_CLK_2") (class "Default")
      (node (ref "IC15") (pin "12") (pinfunction "PC2/OC0C/RXD0_12") (pintype "bidirectional"))
      (node (ref "R22") (pin "1") (pinfunction "1_1") (pintype "passive"))
    )
    (net (code "32") (name "/LED_CLK_3") (class "Default")
      (node (ref "IC15") (pin "13") (pinfunction "PC3/OC0D/TXD0_13") (pintype "bidirectional"))
      (node (ref "R28") (pin "1") (pinfunction "1_1") (pintype "passive"))
    )
    (net (code "33") (name "/LED_CLK_4") (class "Default")
      (node (ref "IC15") (pin "14") (pinfunction "PC4/OC1A/#SS_14") (pintype "bidirectional"))
      (node (ref "R23") (pin "1") (pinfunction "1_1") (pintype "passive"))
    )
    (net (code "34") (name "/LED_CLK_5") (class "Default")
      (node (ref "IC15") (pin "15") (pinfunction "PC5/OC1B/MOSI/XCK1_15") (pintype "bidirectional"))
      (node (ref "R29") (pin "1") (pinfunction "1_1") (pintype "passive"))
    )
    (net (code "35") (name "/LED_LOCK") (class "Default")
      (node (ref "IC15") (pin "24") (pinfunction "~{#SSPD4}_24") (pintype "bidirectional"))
      (node (ref "R24") (pin "1") (pinfunction "1_1") (pintype "passive"))
    )
    (net (code "36") (name "/LED_PWR") (class "Default")
      (node (ref "IC15") (pin "20") (pinfunction "~{OC0APD0}_20") (pintype "bidirectional"))
      (node (ref "R25") (pin "1") (pinfunction "1_1") (pintype "passive"))
    )
    (net (code "37") (name "/LED_REP") (class "Default")
      (node (ref "IC15") (pin "23") (pinfunction "~OC0DTXD0PD3_23") (pintype "bidirectional"))
      (node (ref "R30") (pin "1") (pinfunction "1_1") (pintype "passive"))
    )
    (net (code "38") (name "/PDI-CLK") (class "Default")
      (node (ref "IC15") (pin "35") (pinfunction "RESET/PDI-CLK_35") (pintype "input"))
      (node (ref "PDI") (pin "5") (pinfunction "5_5") (pintype "passive"))
    )
    (net (code "39") (name "/PDI-DATA") (class "Default")
      (node (ref "IC15") (pin "34") (pinfunction "PDI-DATA_34") (pintype "bidirectional"))
      (node (ref "PDI") (pin "1") (pinfunction "1_1") (pintype "passive"))
    )
    (net (code "40") (name "/PWR_GOOD") (class "Default")
      (node (ref "IC15") (pin "4") (pinfunction "PB0/ADC8/AREF_4") (pintype "bidirectional"))
      (node (ref "U2") (pin "6") (pinfunction "P_BAR_6") (pintype "bidirectional"))
    )
    (net (code "41") (name "/RX") (class "Default")
      (node (ref "IC10") (pin "2") (pinfunction "I_2") (pintype "input"))
      (node (ref "R16") (pin "1") (pinfunction "1_1") (pintype "passive"))
      (node (ref "SV1") (pin "6") (pinfunction "6_6") (pintype "passive"))
    )
    (net (code "42") (name "/STATE") (class "Default")
      (node (ref "IC15") (pin "25") (pinfunction "~XCK1MOSIPD5_25") (pintype "bidirectional"))
      (node (ref "R31") (pin "1") (pinfunction "1_1") (pintype "passive"))
    )
    (net (code "43") (name "/TX") (class "Default")
      (node (ref "R10") (pin "1") (pinfunction "1_1") (pintype "passive"))
      (node (ref "SV1") (pin "4") (pinfunction "4_4") (pintype "passive"))
    )
    (net (code "44") (name "/UC_RX") (class "Default")
      (node (ref "IC10") (pin "4") (pinfunction "O_4") (pintype "tri_state"))
      (node (ref "IC15") (pin "2") (pinfunction "PA6/ADC6_2") (pintype "bidirectional"))
    )
    (net (code "45") (name "/UC_TX") (class "Default")
      (node (ref "IC15") (pin "3") (pinfunction "PA7/ADC7/AC0-OUT_3") (pintype "bidirectional"))
      (node (ref "IC18") (pin "2") (pinfunction "I_2") (pintype "input"))
    )
    (net (code "46") (name "/V_BATT") (class "Default")
      (node (ref "BAT_TP") (pin "TP") (pinfunction "TP_TP") (pintype "input"))
      (node (ref "Q1") (pin "1") (pinfunction "S_1") (pintype "passive"))
      (node (ref "R15") (pin "1") (pinfunction "1_1") (pintype "passive"))
      (node (ref "R7") (pin "1") (pinfunction "1_1") (pintype "passive"))
      (node (ref "R8") (pin "2") (pinfunction "2_2") (pintype "passive"))
      (node (ref "U2") (pin "2") (pinfunction "VS_2") (pintype "bidirectional"))
      (node (ref "X1") (pin "2") (pinfunction "S_2") (pintype "passive"))
    )
    (net (code "47") (name "GND") (class "Default")
      (node (ref "C1") (pin "2") (pinfunction "2_2") (pintype "passive"))
      (node (ref "C10") (pin "2") (pinfunction "2_2") (pintype "passive"))
      (node (ref "C11") (pin "2") (pinfunction "2_2") (pintype "passive"))
      (node (ref "C12") (pin "2") (pinfunction "2_2") (pintype "passive"))
      (node (ref "C14") (pin "2") (pinfunction "2_2") (pintype "passive"))
      (node (ref "C16") (pin "2") (pinfunction "2_2") (pintype "passive"))
      (node (ref "C18") (pin "2") (pinfunction "2_2") (pintype "passive"))
      (node (ref "C2") (pin "2") (pinfunction "2_2") (pintype "passive"))
      (node (ref "C20") (pin "2") (pinfunction "2_2") (pintype "passive"))
      (node (ref "C22") (pin "2") (pinfunction "2_2") (pintype "passive"))
      (node (ref "C23") (pin "2") (pinfunction "2_2") (pintype "passive"))
      (node (ref "C24") (pin "2") (pinfunction "2_2") (pintype "passive"))
      (node (ref "C25") (pin "2") (pinfunction "2_2") (pintype "passive"))
      (node (ref "C27") (pin "2") (pinfunction "2_2") (pintype "passive"))
      (node (ref "C28") (pin "2") (pinfunction "2_2") (pintype "passive"))
      (node (ref "C29") (pin "2") (pinfunction "2_2") (pintype "passive"))
      (node (ref "C3") (pin "2") (pinfunction "2_2") (pintype "passive"))
      (node (ref "C30") (pin "2") (pinfunction "2_2") (pintype "passive"))
      (node (ref "C31") (pin "2") (pinfunction "2_2") (pintype "passive"))
      (node (ref "C32") (pin "2") (pinfunction "2_2") (pintype "passive"))
      (node (ref "C33") (pin "2") (pinfunction "2_2") (pintype "passive"))
      (node (ref "C34") (pin "2") (pinfunction "2_2") (pintype "passive"))
      (node (ref "C35") (pin "2") (pinfunction "2_2") (pintype "passive"))
      (node (ref "C36") (pin "2") (pinfunction "2_2") (pintype "passive"))
      (node (ref "C37") (pin "2") (pinfunction "2_2") (pintype "passive"))
      (node (ref "C38") (pin "2") (pinfunction "2_2") (pintype "passive"))
      (node (ref "C4") (pin "2") (pinfunction "2_2") (pintype "passive"))
      (node (ref "C5") (pin "2") (pinfunction "2_2") (pintype "passive"))
      (node (ref "C6") (pin "2") (pinfunction "2_2") (pintype "passive"))
      (node (ref "C62") (pin "2") (pinfunction "2_2") (pintype "passive"))
      (node (ref "C7") (pin "2") (pinfunction "2_2") (pintype "passive"))
      (node (ref "C8") (pin "-") (pinfunction "-_-") (pintype "passive"))
      (node (ref "C9") (pin "2") (pinfunction "2_2") (pintype "passive"))
      (node (ref "CLKIN") (pin "5") (pinfunction "5_5") (pintype "passive"))
      (node (ref "GND_TP0") (pin "TP") (pinfunction "TP_TP") (pintype "input"))
      (node (ref "GND_TP1") (pin "TP") (pinfunction "TP_TP") (pintype "input"))
      (node (ref "IC1") (pin "4") (pinfunction "AGND_4") (pintype "bidirectional"))
      (node (ref "IC10") (pin "1") (pinfunction "OE_1") (pintype "input"))
      (node (ref "IC10") (pin "3") (pinfunction "GND_3") (pintype "power_in"))
      (node (ref "IC11") (pin "4") (pinfunction "AGND_4") (pintype "bidirectional"))
      (node (ref "IC12") (pin "4") (pinfunction "AGND_4") (pintype "bidirectional"))
      (node (ref "IC13") (pin "4") (pinfunction "AGND_4") (pintype "bidirectional"))
      (node (ref "IC14") (pin "4") (pinfunction "AGND_4") (pintype "bidirectional"))
      (node (ref "IC15") (pin "18") (pinfunction "GND_18") (pintype "power_in"))
      (node (ref "IC15") (pin "30") (pinfunction "GND_30") (pintype "power_in"))
      (node (ref "IC15") (pin "38") (pinfunction "GND_38") (pintype "power_in"))
      (node (ref "IC15") (pin "8") (pinfunction "GND_8") (pintype "power_in"))
      (node (ref "IC16") (pin "3") (pinfunction "GND_3") (pintype "power_in"))
      (node (ref "IC18") (pin "3") (pinfunction "GND_3") (pintype "power_in"))
      (node (ref "IC2") (pin "P$2") (pinfunction "GND_P$2") (pintype "bidirectional"))
      (node (ref "IC3") (pin "18") (pinfunction "GND_18") (pintype "power_in"))
      (node (ref "IC3") (pin "21") (pinfunction "GND_21") (pintype "power_in"))
      (node (ref "IC3") (pin "25") (pinfunction "GND_25") (pintype "power_in"))
      (node (ref "IC3") (pin "26") (pinfunction "TEST_26") (pintype "input"))
      (node (ref "IC3") (pin "7") (pinfunction "GND_7") (pintype "power_in"))
      (node (ref "IC4") (pin "2") (pinfunction "GND_2") (pintype "bidirectional"))
      (node (ref "IC5") (pin "2") (pinfunction "GND_2") (pintype "bidirectional"))
      (node (ref "IC6") (pin "4") (pinfunction "AGND_4") (pintype "bidirectional"))
      (node (ref "IC7") (pin "3") (pinfunction "GND_3") (pintype "power_in"))
      (node (ref "IC8") (pin "3") (pinfunction "GND_3") (pintype "power_in"))
      (node (ref "IC9") (pin "3") (pinfunction "GND_3") (pintype "power_in"))
      (node (ref "OSC1") (pin "P$2") (pinfunction "GND_P$2") (pintype "passive"))
      (node (ref "PDI") (pin "6") (pinfunction "6_6") (pintype "passive"))
      (node (ref "Q2") (pin "E") (pinfunction "E_E") (pintype "passive"))
      (node (ref "Q3") (pin "E") (pinfunction "E_E") (pintype "passive"))
      (node (ref "Q4") (pin "1") (pinfunction "S_1") (pintype "passive"))
      (node (ref "R1") (pin "2") (pinfunction "2_2") (pintype "passive"))
      (node (ref "R13") (pin "1") (pinfunction "1_1") (pintype "passive"))
      (node (ref "R16") (pin "2") (pinfunction "2_2") (pintype "passive"))
      (node (ref "R19") (pin "1") (pinfunction "1_1") (pintype "passive"))
      (node (ref "R5") (pin "2") (pinfunction "2_2") (pintype "passive"))
      (node (ref "R54") (pin "2") (pinfunction "2_2") (pintype "passive"))
      (node (ref "SV1") (pin "9") (pinfunction "9_9") (pintype "passive"))
      (node (ref "T10") (pin "2") (pinfunction "E_2") (pintype "passive"))
      (node (ref "T11") (pin "2") (pinfunction "E_2") (pintype "passive"))
      (node (ref "T12") (pin "2") (pinfunction "E_2") (pintype "passive"))
      (node (ref "T13") (pin "2") (pinfunction "E_2") (pintype "passive"))
      (node (ref "T4") (pin "2") (pinfunction "E_2") (pintype "passive"))
      (node (ref "T5") (pin "2") (pinfunction "E_2") (pintype "passive"))
      (node (ref "T6") (pin "2") (pinfunction "E_2") (pintype "passive"))
      (node (ref "T7") (pin "2") (pinfunction "E_2") (pintype "passive"))
      (node (ref "T8") (pin "2") (pinfunction "E_2") (pintype "passive"))
      (node (ref "T9") (pin "2") (pinfunction "E_2") (pintype "passive"))
      (node (ref "TEST") (pin "1") (pinfunction "3_1") (pintype "passive"))
      (node (ref "U1") (pin "2") (pinfunction "VSS_2") (pintype "bidirectional"))
      (node (ref "U2") (pin "4") (pinfunction "GND_4") (pintype "bidirectional"))
      (node (ref "USB") (pin "P$5") (pinfunction "5_P$5") (pintype "bidirectional"))
      (node (ref "X1") (pin "1") (pinfunction "S_1") (pintype "passive"))
    )
    (net (code "48") (name "Net-(CLKIN-Pad1)") (class "Default")
      (node (ref "CLKIN") (pin "1") (pinfunction "1_1") (pintype "passive"))
      (node (ref "R2") (pin "2") (pinfunction "2_2") (pintype "passive"))
      (node (ref "R3") (pin "1") (pinfunction "1_1") (pintype "passive"))
    )
    (net (code "49") (name "Net-(IC1-B1_OUT)") (class "Default")
      (node (ref "CLKOUT1") (pin "4") (pinfunction "4_4") (pintype "passive"))
      (node (ref "IC1") (pin "7") (pinfunction "B1_OUT_7") (pintype "bidirectional"))
    )
    (net (code "50") (name "Net-(IC1-B2_IN)") (class "Default")
      (node (ref "C13") (pin "1") (pinfunction "1_1") (pintype "passive"))
      (node (ref "CLKOUT1") (pin "1") (pinfunction "1_1") (pintype "passive"))
      (node (ref "IC1") (pin "6") (pinfunction "B2_IN_6") (pintype "bidirectional"))
      (node (ref "IC1") (pin "8") (pinfunction "BVDD_8") (pintype "bidirectional"))
    )
    (net (code "51") (name "Net-(IC1-BGND)") (class "Default")
      (node (ref "C13") (pin "2") (pinfunction "2_2") (pintype "passive"))
      (node (ref "CLKOUT1") (pin "5") (pinfunction "5_5") (pintype "passive"))
      (node (ref "IC1") (pin "5") (pinfunction "BGND_5") (pintype "bidirectional"))
    )
    (net (code "52") (name "Net-(IC3-3V3OUT)") (class "Default")
      (node (ref "C7") (pin "1") (pinfunction "1_1") (pintype "passive"))
      (node (ref "IC3") (pin "17") (pinfunction "3V3OUT_17") (pintype "output"))
    )
    (net (code "53") (name "Net-(IC3-USBDM)") (class "Default")
      (node (ref "C6") (pin "1") (pinfunction "1_1") (pintype "passive"))
      (node (ref "IC2") (pin "P$6") (pinfunction "IO1_P$6") (pintype "bidirectional"))
      (node (ref "IC3") (pin "16") (pinfunction "USBDM_16") (pintype "bidirectional"))
    )
    (net (code "54") (name "Net-(IC3-USBDP)") (class "Default")
      (node (ref "C4") (pin "1") (pinfunction "1_1") (pintype "passive"))
      (node (ref "IC2") (pin "P$4") (pinfunction "IO2_P$4") (pintype "bidirectional"))
      (node (ref "IC3") (pin "15") (pinfunction "USBDP_15") (pintype "bidirectional"))
    )
    (net (code "55") (name "Net-(IC3-~{RESET})") (class "Default")
      (node (ref "IC3") (pin "19") (pinfunction "~{RESET}_19") (pintype "input"))
      (node (ref "R18") (pin "2") (pinfunction "2_2") (pintype "passive"))
    )
    (net (code "56") (name "Net-(IC5-OUT)") (class "Default")
      (node (ref "C24") (pin "1") (pinfunction "1_1") (pintype "passive"))
      (node (ref "IC5") (pin "5") (pinfunction "OUT_5") (pintype "bidirectional"))
      (node (ref "R2") (pin "1") (pinfunction "1_1") (pintype "passive"))
    )
    (net (code "57") (name "Net-(IC6-B1_OUT)") (class "Default")
      (node (ref "CLKOUT0") (pin "4") (pinfunction "4_4") (pintype "passive"))
      (node (ref "IC6") (pin "7") (pinfunction "B1_OUT_7") (pintype "bidirectional"))
    )
    (net (code "58") (name "Net-(IC6-B2_IN)") (class "Default")
      (node (ref "C26") (pin "1") (pinfunction "1_1") (pintype "passive"))
      (node (ref "CLKOUT0") (pin "1") (pinfunction "1_1") (pintype "passive"))
      (node (ref "IC6") (pin "6") (pinfunction "B2_IN_6") (pintype "bidirectional"))
      (node (ref "IC6") (pin "8") (pinfunction "BVDD_8") (pintype "bidirectional"))
    )
    (net (code "59") (name "Net-(IC6-BGND)") (class "Default")
      (node (ref "C26") (pin "2") (pinfunction "2_2") (pintype "passive"))
      (node (ref "CLKOUT0") (pin "5") (pinfunction "5_5") (pintype "passive"))
      (node (ref "IC6") (pin "5") (pinfunction "BGND_5") (pintype "bidirectional"))
    )
    (net (code "60") (name "Net-(IC7A-O)") (class "Default")
      (node (ref "IC7") (pin "4") (pinfunction "O_4") (pintype "output"))
      (node (ref "R11") (pin "2") (pinfunction "2_2") (pintype "passive"))
    )
    (net (code "61") (name "Net-(IC11-B1_OUT)") (class "Default")
      (node (ref "CLKOUT2") (pin "4") (pinfunction "4_4") (pintype "passive"))
      (node (ref "IC11") (pin "7") (pinfunction "B1_OUT_7") (pintype "bidirectional"))
    )
    (net (code "62") (name "Net-(IC11-B2_IN)") (class "Default")
      (node (ref "C15") (pin "1") (pinfunction "1_1") (pintype "passive"))
      (node (ref "CLKOUT2") (pin "1") (pinfunction "1_1") (pintype "passive"))
      (node (ref "IC11") (pin "6") (pinfunction "B2_IN_6") (pintype "bidirectional"))
      (node (ref "IC11") (pin "8") (pinfunction "BVDD_8") (pintype "bidirectional"))
    )
    (net (code "63") (name "Net-(IC11-BGND)") (class "Default")
      (node (ref "C15") (pin "2") (pinfunction "2_2") (pintype "passive"))
      (node (ref "CLKOUT2") (pin "5") (pinfunction "5_5") (pintype "passive"))
      (node (ref "IC11") (pin "5") (pinfunction "BGND_5") (pintype "bidirectional"))
    )
    (net (code "64") (name "Net-(IC12-B1_OUT)") (class "Default")
      (node (ref "CLKOUT3") (pin "4") (pinfunction "4_4") (pintype "passive"))
      (node (ref "IC12") (pin "7") (pinfunction "B1_OUT_7") (pintype "bidirectional"))
    )
    (net (code "65") (name "Net-(IC12-B2_IN)") (class "Default")
      (node (ref "C17") (pin "1") (pinfunction "1_1") (pintype "passive"))
      (node (ref "CLKOUT3") (pin "1") (pinfunction "1_1") (pintype "passive"))
      (node (ref "IC12") (pin "6") (pinfunction "B2_IN_6") (pintype "bidirectional"))
      (node (ref "IC12") (pin "8") (pinfunction "BVDD_8") (pintype "bidirectional"))
    )
    (net (code "66") (name "Net-(IC12-BGND)") (class "Default")
      (node (ref "C17") (pin "2") (pinfunction "2_2") (pintype "passive"))
      (node (ref "CLKOUT3") (pin "5") (pinfunction "5_5") (pintype "passive"))
      (node (ref "IC12") (pin "5") (pinfunction "BGND_5") (pintype "bidirectional"))
    )
    (net (code "67") (name "Net-(IC13-B1_OUT)") (class "Default")
      (node (ref "CLKOUT4") (pin "4") (pinfunction "4_4") (pintype "passive"))
      (node (ref "IC13") (pin "7") (pinfunction "B1_OUT_7") (pintype "bidirectional"))
    )
    (net (code "68") (name "Net-(IC13-B2_IN)") (class "Default")
      (node (ref "C19") (pin "1") (pinfunction "1_1") (pintype "passive"))
      (node (ref "CLKOUT4") (pin "1") (pinfunction "1_1") (pintype "passive"))
      (node (ref "IC13") (pin "6") (pinfunction "B2_IN_6") (pintype "bidirectional"))
      (node (ref "IC13") (pin "8") (pinfunction "BVDD_8") (pintype "bidirectional"))
    )
    (net (code "69") (name "Net-(IC13-BGND)") (class "Default")
      (node (ref "C19") (pin "2") (pinfunction "2_2") (pintype "passive"))
      (node (ref "CLKOUT4") (pin "5") (pinfunction "5_5") (pintype "passive"))
      (node (ref "IC13") (pin "5") (pinfunction "BGND_5") (pintype "bidirectional"))
    )
    (net (code "70") (name "Net-(IC14-B1_OUT)") (class "Default")
      (node (ref "CLKOUT5") (pin "4") (pinfunction "4_4") (pintype "passive"))
      (node (ref "IC14") (pin "7") (pinfunction "B1_OUT_7") (pintype "bidirectional"))
    )
    (net (code "71") (name "Net-(IC14-B2_IN)") (class "Default")
      (node (ref "C21") (pin "1") (pinfunction "1_1") (pintype "passive"))
      (node (ref "CLKOUT5") (pin "1") (pinfunction "1_1") (pintype "passive"))
      (node (ref "IC14") (pin "6") (pinfunction "B2_IN_6") (pintype "bidirectional"))
      (node (ref "IC14") (pin "8") (pinfunction "BVDD_8") (pintype "bidirectional"))
    )
    (net (code "72") (name "Net-(IC14-BGND)") (class "Default")
      (node (ref "C21") (pin "2") (pinfunction "2_2") (pintype "passive"))
      (node (ref "CLKOUT5") (pin "5") (pinfunction "5_5") (pintype "passive"))
      (node (ref "IC14") (pin "5") (pinfunction "BGND_5") (pintype "bidirectional"))
    )
    (net (code "73") (name "Net-(IC15-PR1{slash}XTAL1)") (class "Default")
      (node (ref "IC15") (pin "37") (pinfunction "PR1/XTAL1_37") (pintype "bidirectional"))
      (node (ref "OSC1") (pin "P$3") (pinfunction "OUTPUT_P$3") (pintype "passive"))
    )
    (net (code "74") (name "Net-(IC16A-O)") (class "Default")
      (node (ref "IC16") (pin "4") (pinfunction "O_4") (pintype "output"))
      (node (ref "R12") (pin "2") (pinfunction "2_2") (pintype "passive"))
    )
    (net (code "75") (name "Net-(IC18A-O)") (class "Default")
      (node (ref "IC18") (pin "4") (pinfunction "O_4") (pintype "output"))
      (node (ref "R10") (pin "2") (pinfunction "2_2") (pintype "passive"))
    )
    (net (code "76") (name "Net-(LED1A-C)") (class "Default")
      (node (ref "LED1") (pin "C1") (pinfunction "C_C1") (pintype "passive"))
      (node (ref "R40") (pin "1") (pinfunction "1_1") (pintype "passive"))
    )
    (net (code "77") (name "Net-(LED1B-C)") (class "Default")
      (node (ref "LED1") (pin "C2") (pinfunction "C_C2") (pintype "passive"))
      (node (ref "R33") (pin "1") (pinfunction "1_1") (pintype "passive"))
    )
    (net (code "78") (name "Net-(LED2A-C)") (class "Default")
      (node (ref "LED2") (pin "C1") (pinfunction "C_C1") (pintype "passive"))
      (node (ref "R41") (pin "1") (pinfunction "1_1") (pintype "passive"))
    )
    (net (code "79") (name "Net-(LED2B-C)") (class "Default")
      (node (ref "LED2") (pin "C2") (pinfunction "C_C2") (pintype "passive"))
      (node (ref "R34") (pin "1") (pinfunction "1_1") (pintype "passive"))
    )
    (net (code "80") (name "Net-(LED3A-C)") (class "Default")
      (node (ref "LED3") (pin "C1") (pinfunction "C_C1") (pintype "passive"))
      (node (ref "R42") (pin "1") (pinfunction "1_1") (pintype "passive"))
    )
    (net (code "81") (name "Net-(LED3B-C)") (class "Default")
      (node (ref "LED3") (pin "C2") (pinfunction "C_C2") (pintype "passive"))
      (node (ref "R35") (pin "1") (pinfunction "1_1") (pintype "passive"))
    )
    (net (code "82") (name "Net-(LED4A-C)") (class "Default")
      (node (ref "LED4") (pin "C1") (pinfunction "C_C1") (pintype "passive"))
      (node (ref "R44") (pin "1") (pinfunction "1_1") (pintype "passive"))
    )
    (net (code "83") (name "Net-(LED4B-C)") (class "Default")
      (node (ref "LED4") (pin "C2") (pinfunction "C_C2") (pintype "passive"))
      (node (ref "R36") (pin "1") (pinfunction "1_1") (pintype "passive"))
    )
    (net (code "84") (name "Net-(LED5A-C)") (class "Default")
      (node (ref "LED5") (pin "C1") (pinfunction "C_C1") (pintype "passive"))
      (node (ref "R45") (pin "1") (pinfunction "1_1") (pintype "passive"))
    )
    (net (code "85") (name "Net-(LED5B-C)") (class "Default")
      (node (ref "LED5") (pin "C2") (pinfunction "C_C2") (pintype "passive"))
      (node (ref "R37") (pin "1") (pinfunction "1_1") (pintype "passive"))
    )
    (net (code "86") (name "Net-(Q1-D)") (class "Default")
      (node (ref "Q1") (pin "3") (pinfunction "D_3") (pintype "passive"))
      (node (ref "R4") (pin "1") (pinfunction "1_1") (pintype "passive"))
    )
    (net (code "87") (name "Net-(Q1-G)") (class "Default")
      (node (ref "Q1") (pin "2") (pinfunction "G_2") (pintype "passive"))
      (node (ref "Q2") (pin "C") (pinfunction "C_C") (pintype "passive"))
      (node (ref "R7") (pin "2") (pinfunction "2_2") (pintype "passive"))
    )
    (net (code "88") (name "Net-(Q2-PadB)") (class "Default")
      (node (ref "Q2") (pin "B") (pinfunction "B_B") (pintype "passive"))
      (node (ref "R6") (pin "2") (pinfunction "2_2") (pintype "passive"))
    )
    (net (code "89") (name "Net-(Q3-PadB)") (class "Default")
      (node (ref "Q3") (pin "B") (pinfunction "B_B") (pintype "passive"))
      (node (ref "R14") (pin "2") (pinfunction "2_2") (pintype "passive"))
    )
    (net (code "90") (name "Net-(Q3-PadC)") (class "Default")
      (node (ref "Q3") (pin "C") (pinfunction "C_C") (pintype "passive"))
      (node (ref "R15") (pin "2") (pinfunction "2_2") (pintype "passive"))
    )
    (net (code "91") (name "Net-(Q4-D)") (class "Default")
      (node (ref "Q4") (pin "3") (pinfunction "D_3") (pintype "passive"))
      (node (ref "Q6") (pin "2") (pinfunction "G_2") (pintype "passive"))
      (node (ref "R17") (pin "1") (pinfunction "1_1") (pintype "passive"))
    )
    (net (code "92") (name "Net-(Q6-D)") (class "Default")
      (node (ref "Q6") (pin "3") (pinfunction "D_3") (pintype "passive"))
      (node (ref "U1") (pin "4") (pinfunction "VDD_4") (pintype "bidirectional"))
    )
    (net (code "93") (name "Net-(R9-Pad1)") (class "Default")
      (node (ref "R9") (pin "1") (pinfunction "1_1") (pintype "passive"))
      (node (ref "TEST") (pin "2") (pinfunction "2_2") (pintype "passive"))
    )
    (net (code "94") (name "Net-(T4-B)") (class "Default")
      (node (ref "R21") (pin "2") (pinfunction "2_2") (pintype "passive"))
      (node (ref "T4") (pin "1") (pinfunction "B_1") (pintype "passive"))
    )
    (net (code "95") (name "Net-(T4-C)") (class "Default")
      (node (ref "R33") (pin "2") (pinfunction "2_2") (pintype "passive"))
      (node (ref "T4") (pin "3") (pinfunction "C_3") (pintype "passive"))
    )
    (net (code "96") (name "Net-(T5-B)") (class "Default")
      (node (ref "R27") (pin "2") (pinfunction "2_2") (pintype "passive"))
      (node (ref "T5") (pin "1") (pinfunction "B_1") (pintype "passive"))
    )
    (net (code "97") (name "Net-(T5-C)") (class "Default")
      (node (ref "R40") (pin "2") (pinfunction "2_2") (pintype "passive"))
      (node (ref "T5") (pin "3") (pinfunction "C_3") (pintype "passive"))
    )
    (net (code "98") (name "Net-(T6-B)") (class "Default")
      (node (ref "R22") (pin "2") (pinfunction "2_2") (pintype "passive"))
      (node (ref "T6") (pin "1") (pinfunction "B_1") (pintype "passive"))
    )
    (net (code "99") (name "Net-(T6-C)") (class "Default")
      (node (ref "R34") (pin "2") (pinfunction "2_2") (pintype "passive"))
      (node (ref "T6") (pin "3") (pinfunction "C_3") (pintype "passive"))
    )
    (net (code "100") (name "Net-(T7-B)") (class "Default")
      (node (ref "R28") (pin "2") (pinfunction "2_2") (pintype "passive"))
      (node (ref "T7") (pin "1") (pinfunction "B_1") (pintype "passive"))
    )
    (net (code "101") (name "Net-(T7-C)") (class "Default")
      (node (ref "R41") (pin "2") (pinfunction "2_2") (pintype "passive"))
      (node (ref "T7") (pin "3") (pinfunction "C_3") (pintype "passive"))
    )
    (net (code "102") (name "Net-(T8-B)") (class "Default")
      (node (ref "R23") (pin "2") (pinfunction "2_2") (pintype "passive"))
      (node (ref "T8") (pin "1") (pinfunction "B_1") (pintype "passive"))
    )
    (net (code "103") (name "Net-(T8-C)") (class "Default")
      (node (ref "R35") (pin "2") (pinfunction "2_2") (pintype "passive"))
      (node (ref "T8") (pin "3") (pinfunction "C_3") (pintype "passive"))
    )
    (net (code "104") (name "Net-(T9-B)") (class "Default")
      (node (ref "R29") (pin "2") (pinfunction "2_2") (pintype "passive"))
      (node (ref "T9") (pin "1") (pinfunction "B_1") (pintype "passive"))
    )
    (net (code "105") (name "Net-(T9-C)") (class "Default")
      (node (ref "R42") (pin "2") (pinfunction "2_2") (pintype "passive"))
      (node (ref "T9") (pin "3") (pinfunction "C_3") (pintype "passive"))
    )
    (net (code "106") (name "Net-(T10-B)") (class "Default")
      (node (ref "R24") (pin "2") (pinfunction "2_2") (pintype "passive"))
      (node (ref "T10") (pin "1") (pinfunction "B_1") (pintype "passive"))
    )
    (net (code "107") (name "Net-(T10-C)") (class "Default")
      (node (ref "R36") (pin "2") (pinfunction "2_2") (pintype "passive"))
      (node (ref "T10") (pin "3") (pinfunction "C_3") (pintype "passive"))
    )
    (net (code "108") (name "Net-(T11-B)") (class "Default")
      (node (ref "R30") (pin "2") (pinfunction "2_2") (pintype "passive"))
      (node (ref "T11") (pin "1") (pinfunction "B_1") (pintype "passive"))
    )
    (net (code "109") (name "Net-(T11-C)") (class "Default")
      (node (ref "R44") (pin "2") (pinfunction "2_2") (pintype "passive"))
      (node (ref "T11") (pin "3") (pinfunction "C_3") (pintype "passive"))
    )
    (net (code "110") (name "Net-(T12-B)") (class "Default")
      (node (ref "R25") (pin "2") (pinfunction "2_2") (pintype "passive"))
      (node (ref "T12") (pin "1") (pinfunction "B_1") (pintype "passive"))
    )
    (net (code "111") (name "Net-(T12-C)") (class "Default")
      (node (ref "R37") (pin "2") (pinfunction "2_2") (pintype "passive"))
      (node (ref "T12") (pin "3") (pinfunction "C_3") (pintype "passive"))
    )
    (net (code "112") (name "Net-(T13-B)") (class "Default")
      (node (ref "R31") (pin "2") (pinfunction "2_2") (pintype "passive"))
      (node (ref "T13") (pin "1") (pinfunction "B_1") (pintype "passive"))
    )
    (net (code "113") (name "Net-(T13-C)") (class "Default")
      (node (ref "R45") (pin "2") (pinfunction "2_2") (pintype "passive"))
      (node (ref "T13") (pin "3") (pinfunction "C_3") (pintype "passive"))
    )
    (net (code "114") (name "Net-(U1-PROG)") (class "Default")
      (node (ref "R13") (pin "2") (pinfunction "2_2") (pintype "passive"))
      (node (ref "U1") (pin "5") (pinfunction "PROG_5") (pintype "bidirectional"))
    )
    (net (code "115") (name "Net-(U1-VBAT)") (class "Default")
      (node (ref "R8") (pin "1") (pinfunction "1_1") (pintype "passive"))
      (node (ref "U1") (pin "3") (pinfunction "VBAT_3") (pintype "bidirectional"))
    )
    (net (code "116") (name "Net-(USB-2)") (class "Default")
      (node (ref "IC2") (pin "P$1") (pinfunction "IO1_P$1") (pintype "bidirectional"))
      (node (ref "USB") (pin "P$2") (pinfunction "2_P$2") (pintype "bidirectional"))
    )
    (net (code "117") (name "Net-(USB-3)") (class "Default")
      (node (ref "IC2") (pin "P$3") (pinfunction "IO2_P$3") (pintype "bidirectional"))
      (node (ref "USB") (pin "P$3") (pinfunction "3_P$3") (pintype "bidirectional"))
    )
    (net (code "118") (name "Net-(USB-P$1)") (class "Default")
      (node (ref "R1") (pin "1") (pinfunction "1_1") (pintype "passive"))
      (node (ref "USB") (pin "SHIELD_1") (pinfunction "P$1_SHIELD_1") (pintype "bidirectional"))
    )
    (net (code "119") (name "Net-(USB-P$4)") (class "Default")
      (node (ref "C2") (pin "1") (pinfunction "1_1") (pintype "passive"))
      (node (ref "USB") (pin "SHIELD_4") (pinfunction "P$4_SHIELD_4") (pintype "bidirectional"))
    )
    (net (code "120") (name "unconnected-(IC3-CBUS0-Pad23)") (class "Default")
      (node (ref "IC3") (pin "23") (pinfunction "CBUS0_23") (pintype "bidirectional"))
    )
    (net (code "121") (name "unconnected-(IC3-CBUS1-Pad22)") (class "Default")
      (node (ref "IC3") (pin "22") (pinfunction "CBUS1_22") (pintype "bidirectional"))
    )
    (net (code "122") (name "unconnected-(IC3-CBUS2-Pad13)") (class "Default")
      (node (ref "IC3") (pin "13") (pinfunction "CBUS2_13") (pintype "bidirectional"))
    )
    (net (code "123") (name "unconnected-(IC3-CBUS3-Pad14)") (class "Default")
      (node (ref "IC3") (pin "14") (pinfunction "CBUS3_14") (pintype "bidirectional"))
    )
    (net (code "124") (name "unconnected-(IC3-CBUS4-Pad12)") (class "Default")
      (node (ref "IC3") (pin "12") (pinfunction "CBUS4_12") (pintype "bidirectional"))
    )
    (net (code "125") (name "unconnected-(IC3-OSCI-Pad27)") (class "Default")
      (node (ref "IC3") (pin "27") (pinfunction "OSCI_27") (pintype "input"))
    )
    (net (code "126") (name "unconnected-(IC3-OSCO-Pad28)") (class "Default")
      (node (ref "IC3") (pin "28") (pinfunction "OSCO_28") (pintype "output"))
    )
    (net (code "127") (name "unconnected-(IC3-~{DCD}-Pad10)") (class "Default")
      (node (ref "IC3") (pin "10") (pinfunction "~{DCD}_10") (pintype "input"))
    )
    (net (code "128") (name "unconnected-(IC3-~{DSR}-Pad9)") (class "Default")
      (node (ref "IC3") (pin "9") (pinfunction "~{DSR}_9") (pintype "input"))
    )
    (net (code "129") (name "unconnected-(IC3-~{DTR}-Pad2)") (class "Default")
      (node (ref "IC3") (pin "2") (pinfunction "~{DTR}_2") (pintype "output"))
    )
    (net (code "130") (name "unconnected-(IC3-~{RI}-Pad6)") (class "Default")
      (node (ref "IC3") (pin "6") (pinfunction "~{RI}_6") (pintype "input"))
    )
    (net (code "131") (name "unconnected-(IC4-N{slash}C-Pad4)") (class "Default")
      (node (ref "IC4") (pin "4") (pinfunction "N/C_4") (pintype "bidirectional"))
    )
    (net (code "132") (name "unconnected-(IC5-N{slash}C-Pad4)") (class "Default")
      (node (ref "IC5") (pin "4") (pinfunction "N/C_4") (pintype "bidirectional"))
    )
    (net (code "133") (name "unconnected-(IC7A-OE-Pad1)") (class "Default")
      (node (ref "IC7") (pin "1") (pinfunction "OE_1") (pintype "input"))
    )
    (net (code "134") (name "unconnected-(IC16A-OE-Pad1)") (class "Default")
      (node (ref "IC16") (pin "1") (pinfunction "OE_1") (pintype "input"))
    )
    (net (code "135") (name "unconnected-(IC18A-OE-Pad1)") (class "Default")
      (node (ref "IC18") (pin "1") (pinfunction "OE_1") (pintype "input"))
    )
    (net (code "136") (name "unconnected-(OSC1-STANDBY#-PadP$1)") (class "Default")
      (node (ref "OSC1") (pin "P$1") (pinfunction "STANDBY#_P$1") (pintype "passive"))
    )
    (net (code "137") (name "unconnected-(PDI-Pad3)") (class "Default")
      (node (ref "PDI") (pin "3") (pinfunction "3_3") (pintype "passive"))
    )
    (net (code "138") (name "unconnected-(PDI-Pad4)") (class "Default")
      (node (ref "PDI") (pin "4") (pinfunction "4_4") (pintype "passive"))
    )
    (net (code "139") (name "unconnected-(SV1-Pad3)") (class "Default")
      (node (ref "SV1") (pin "3") (pinfunction "3_3") (pintype "passive"))
    )
    (net (code "140") (name "unconnected-(SV1-Pad5)") (class "Default")
      (node (ref "SV1") (pin "5") (pinfunction "5_5") (pintype "passive"))
    )
    (net (code "141") (name "unconnected-(SV1-Pad7)") (class "Default")
      (node (ref "SV1") (pin "7") (pinfunction "7_7") (pintype "passive"))
    )
    (net (code "142") (name "unconnected-(SV1-Pad8)") (class "Default")
      (node (ref "SV1") (pin "8") (pinfunction "8_8") (pintype "passive"))
    )
    (net (code "143") (name "unconnected-(TEST-1-Pad3)") (class "Default")
      (node (ref "TEST") (pin "3") (pinfunction "1_3") (pintype "passive"))
    )
    (net (code "144") (name "unconnected-(U1-STAT-Pad1)") (class "Default")
      (node (ref "U1") (pin "1") (pinfunction "STAT_1") (pintype "bidirectional"))
    )
    (net (code "145") (name "unconnected-(U2-NC5-Pad5)") (class "Default")
      (node (ref "U2") (pin "5") (pinfunction "NC5_5") (pintype "bidirectional"))
    )
    (net (code "146") (name "unconnected-(U2-NC7-Pad7)") (class "Default")
      (node (ref "U2") (pin "7") (pinfunction "NC7_7") (pintype "bidirectional"))
    )
    (net (code "147") (name "unconnected-(U2-S_BAR-Pad3)") (class "Default")
      (node (ref "U2") (pin "3") (pinfunction "S_BAR_3") (pintype "bidirectional"))
    )
    (net (code "148") (name "unconnected-(USB-4-PadP$4)") (class "Default")
      (node (ref "USB") (pin "P$4") (pinfunction "4_P$4") (pintype "bidirectional"))
    )
    (net (code "149") (name "unconnected-(USB-P$2-PadSHIELD_2)") (class "Default")
      (node (ref "USB") (pin "SHIELD_2") (pinfunction "P$2_SHIELD_2") (pintype "bidirectional"))
    )
    (net (code "150") (name "unconnected-(USB-P$3-PadSHIELD_3)") (class "Default")
      (node (ref "USB") (pin "SHIELD_3") (pinfunction "P$3_SHIELD_3") (pintype "bidirectional"))
    )
  )
)
